# OpenCardiographySignalMeasuringDevice.net
KiCad netlist of a schematic drawn in EasyEDA Pro
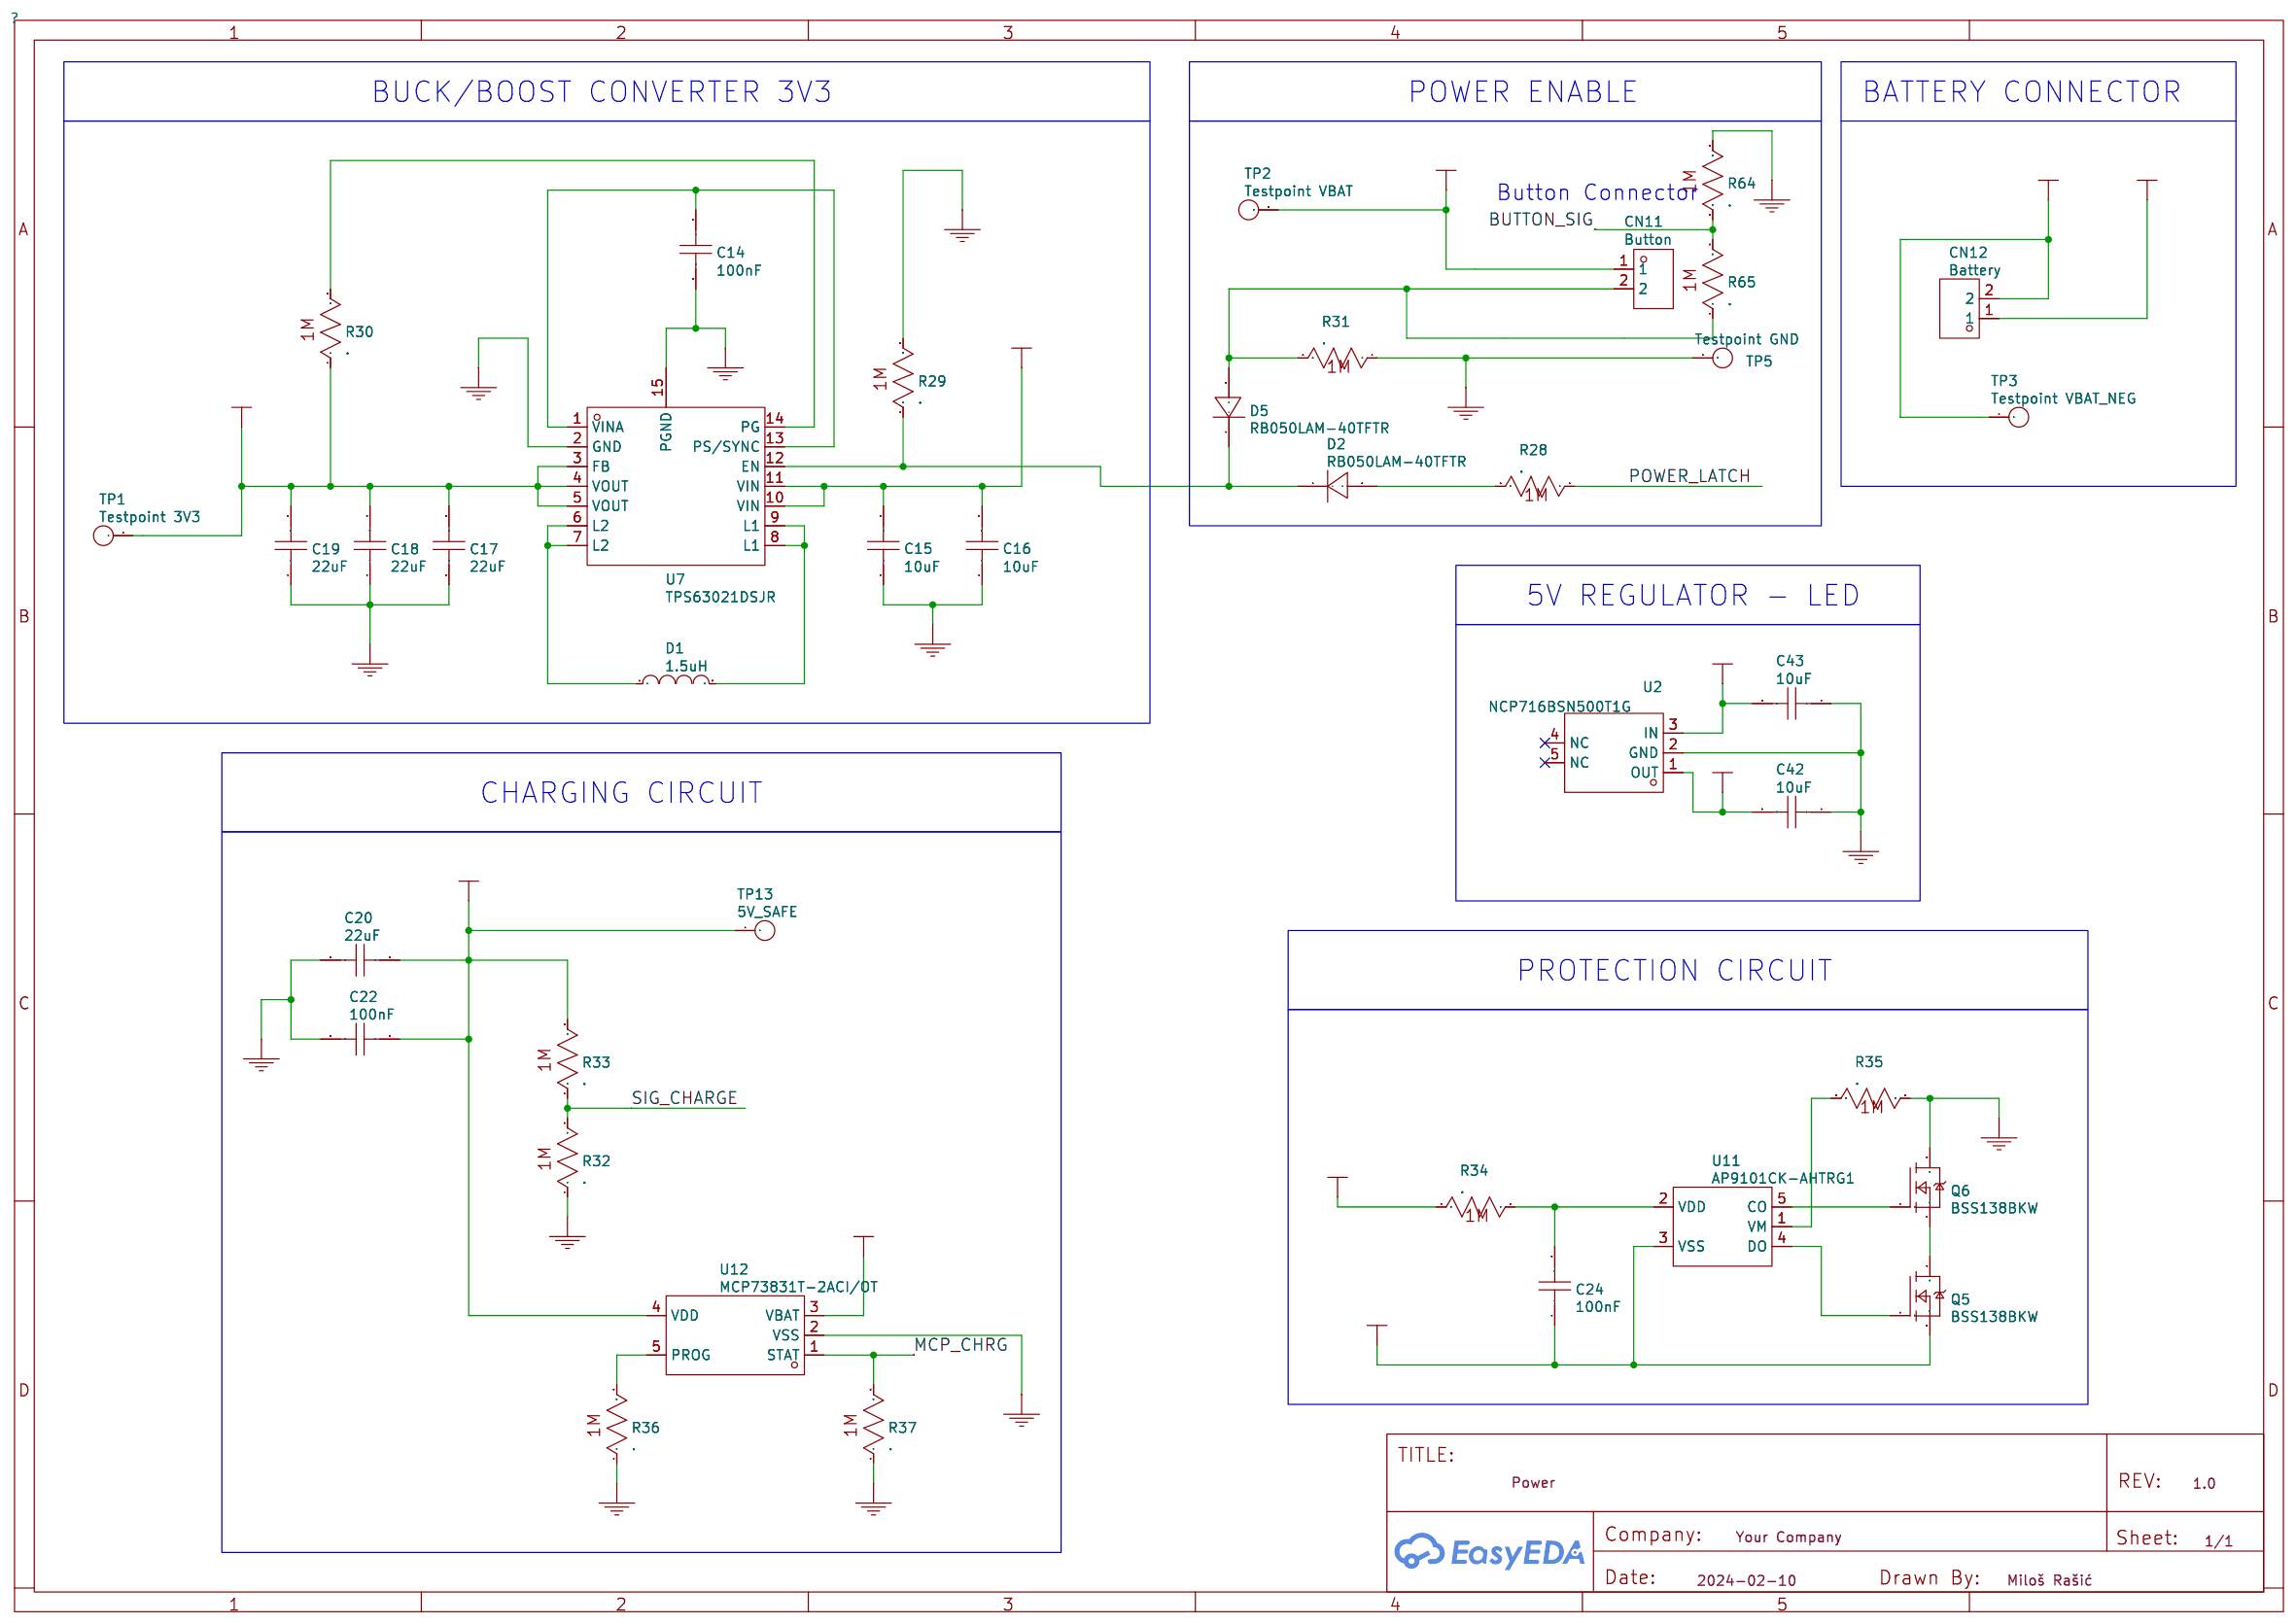
[diagram p0: Power]
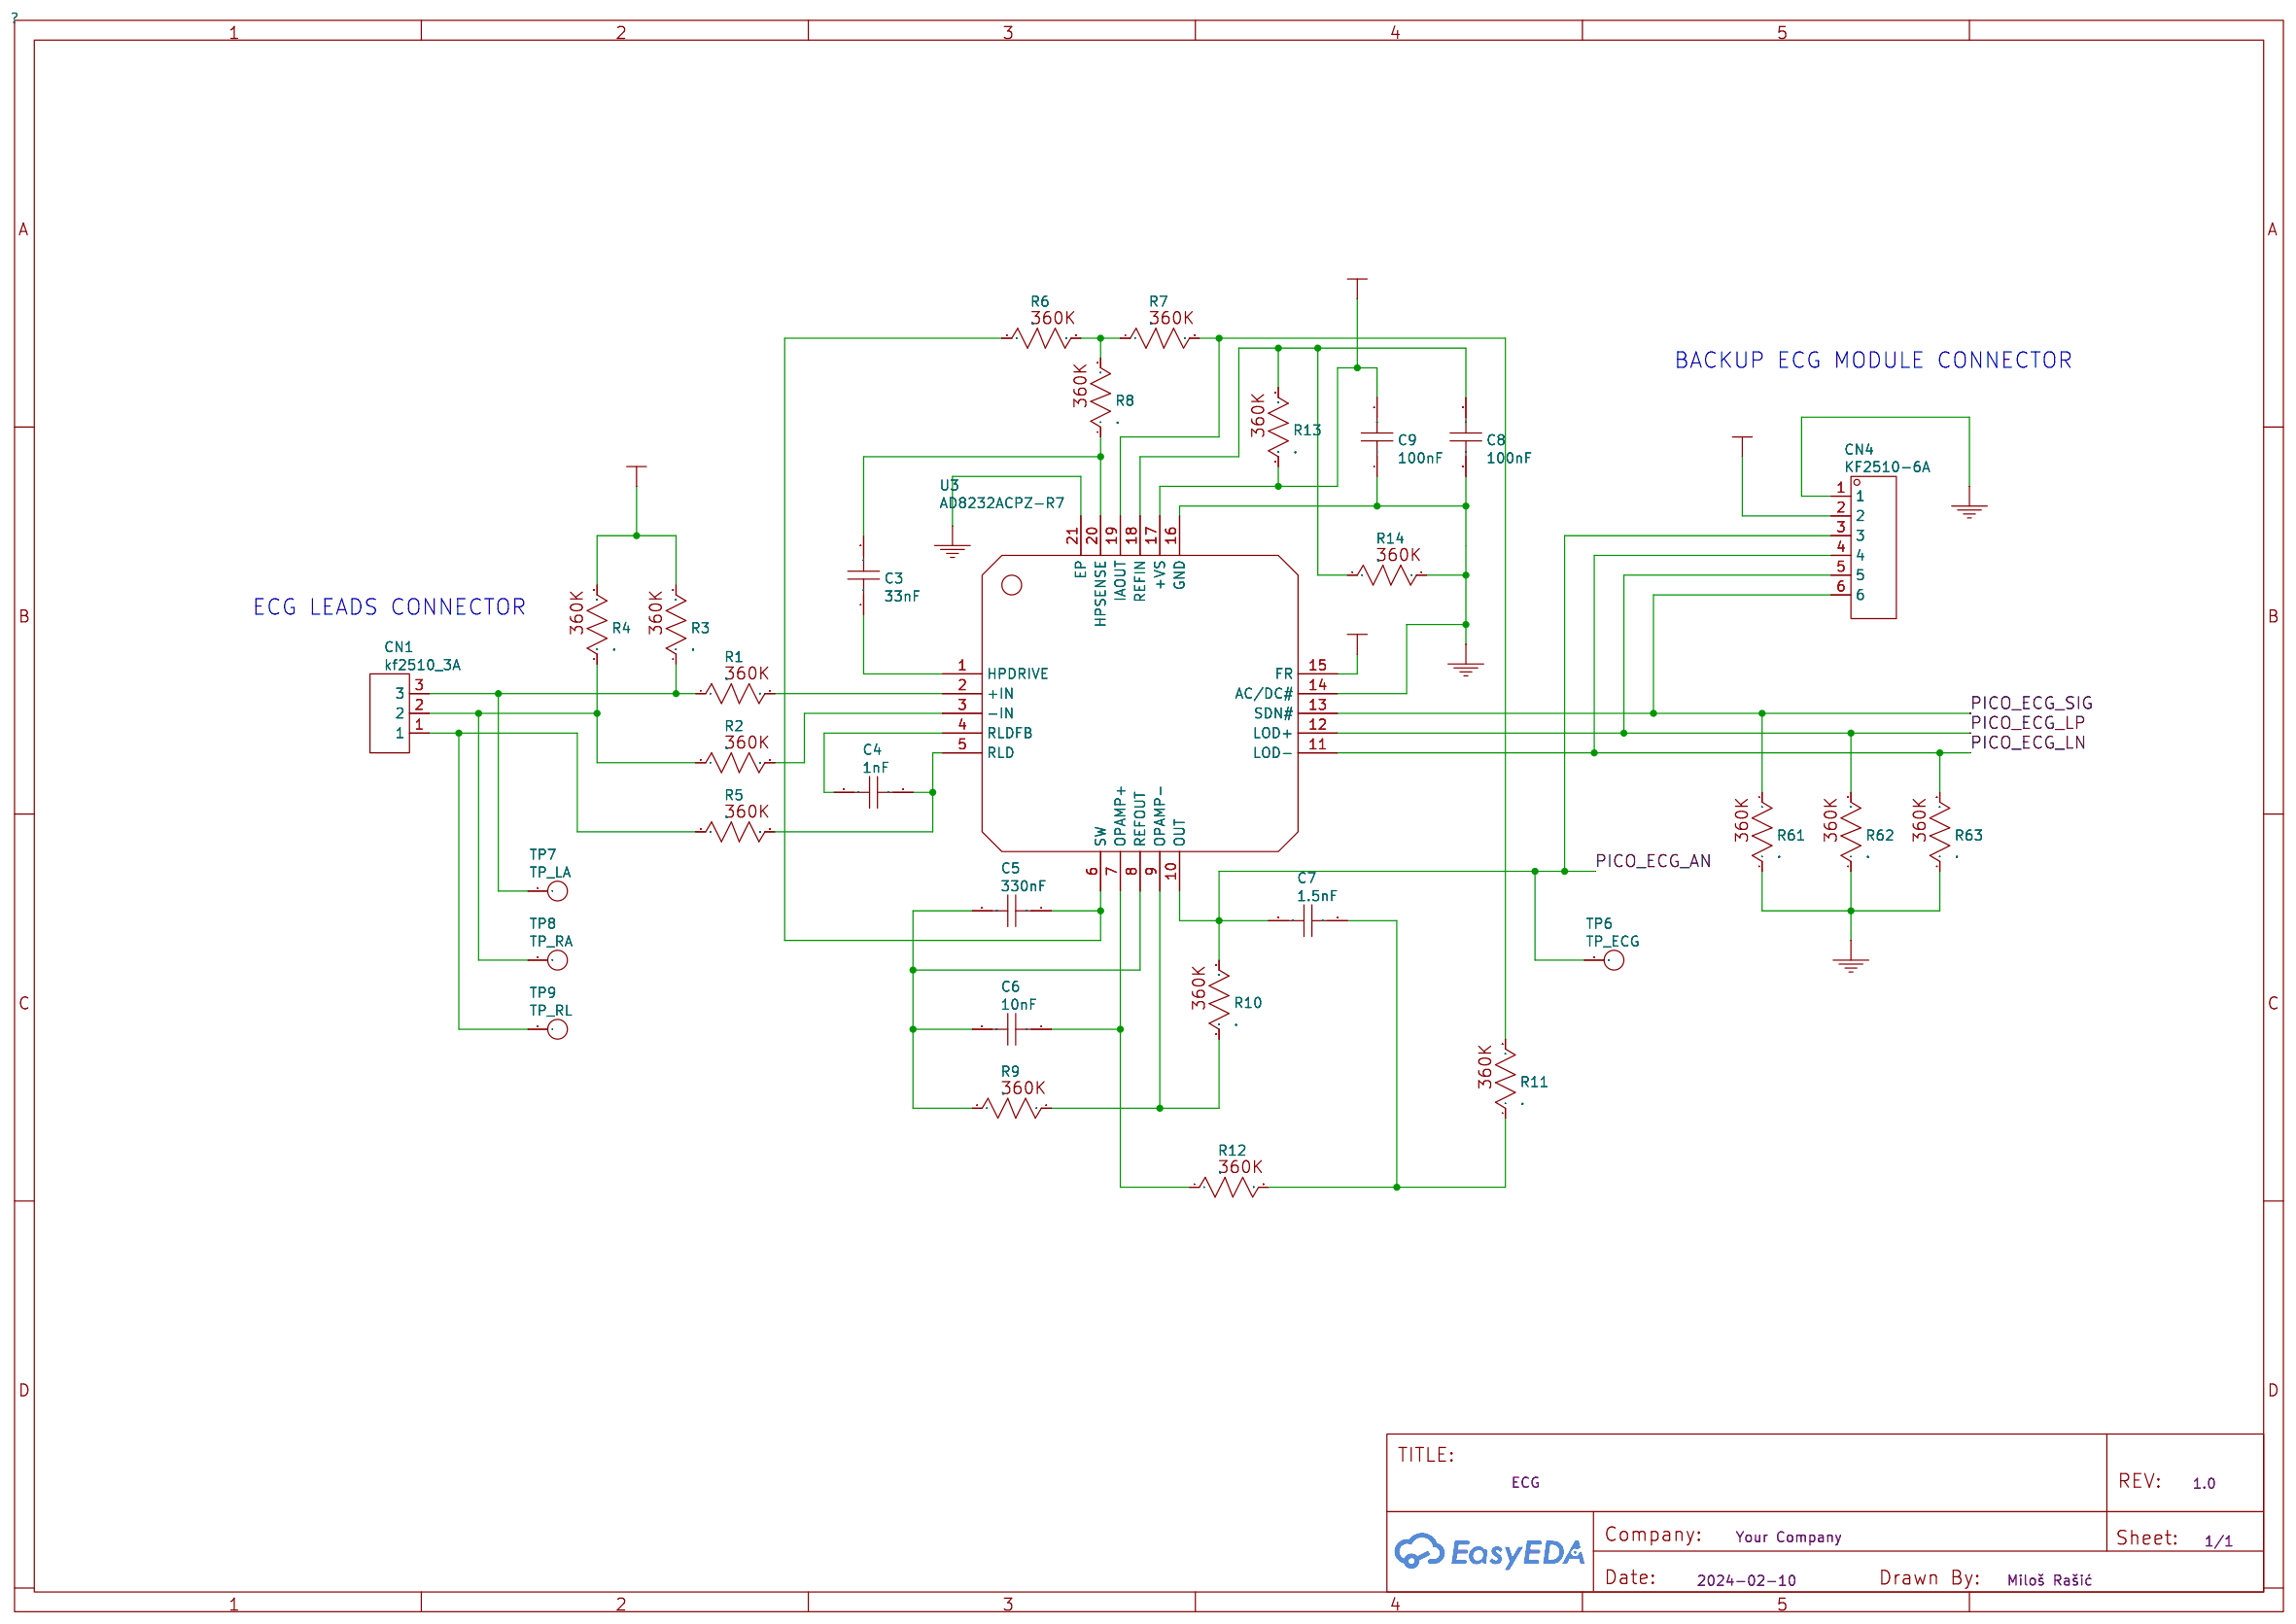
[diagram p1: ECG]
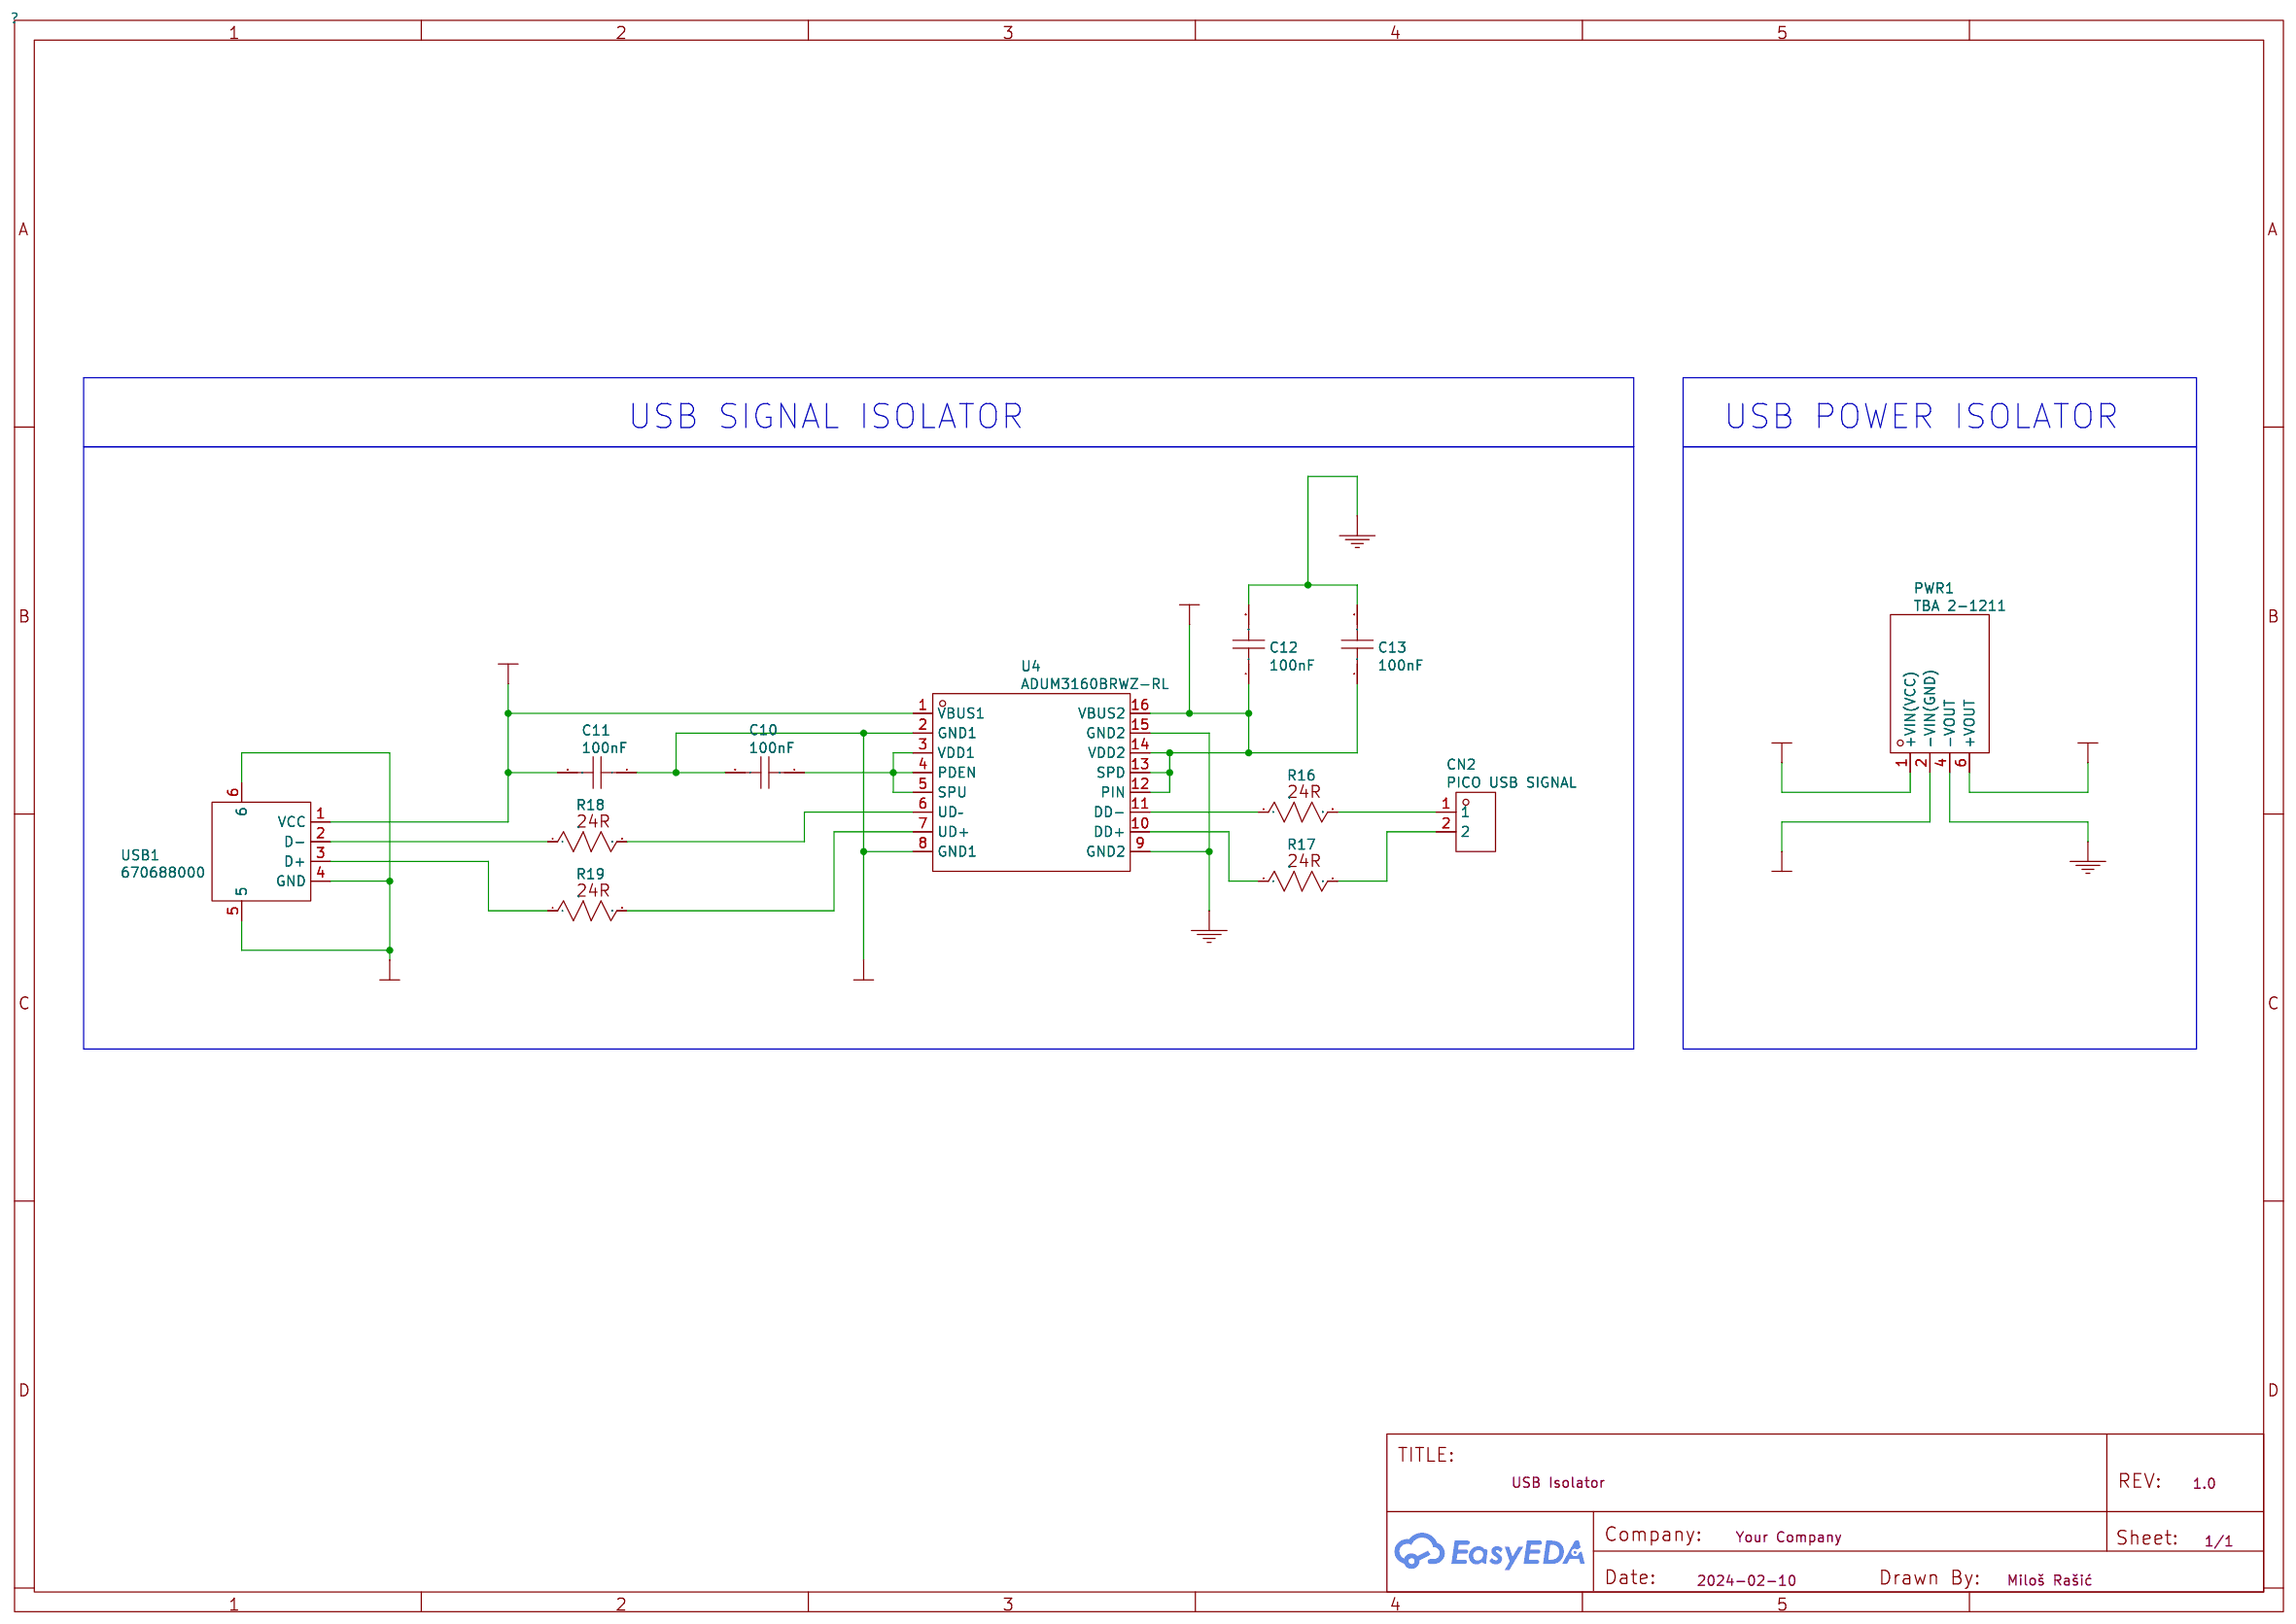
[diagram p2: USB Isolator]
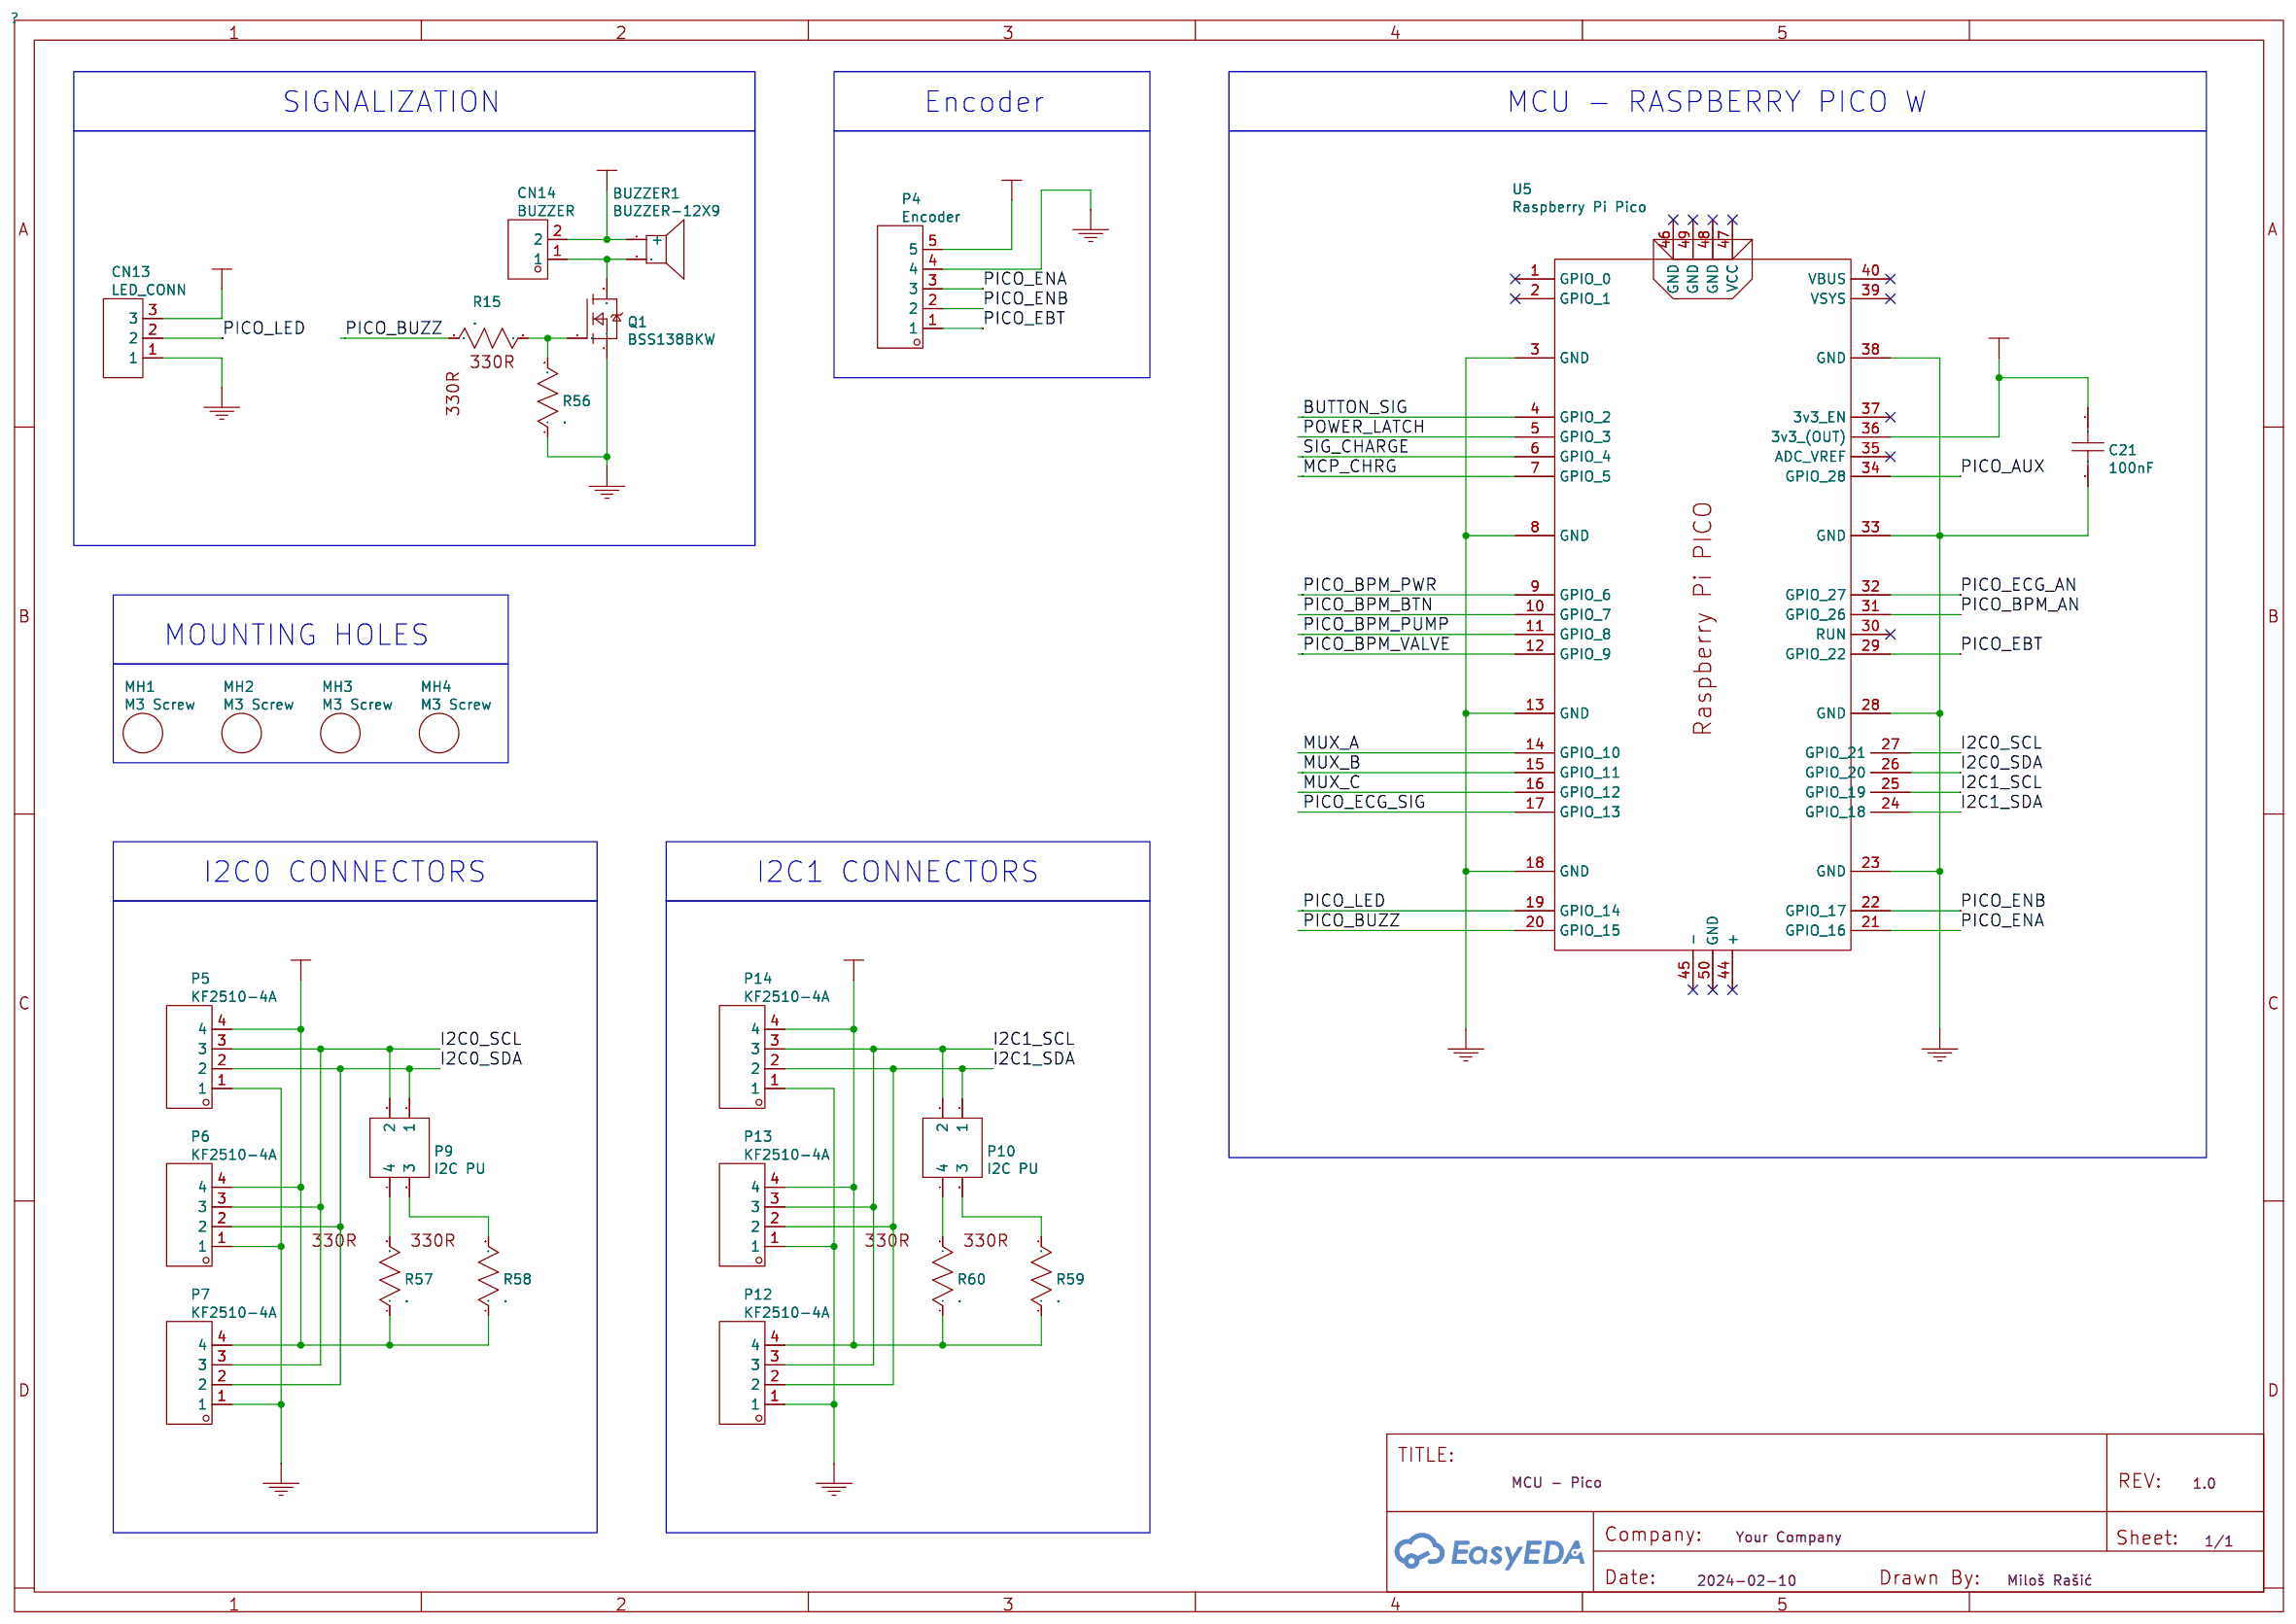
[diagram p3: MCU - Pico]
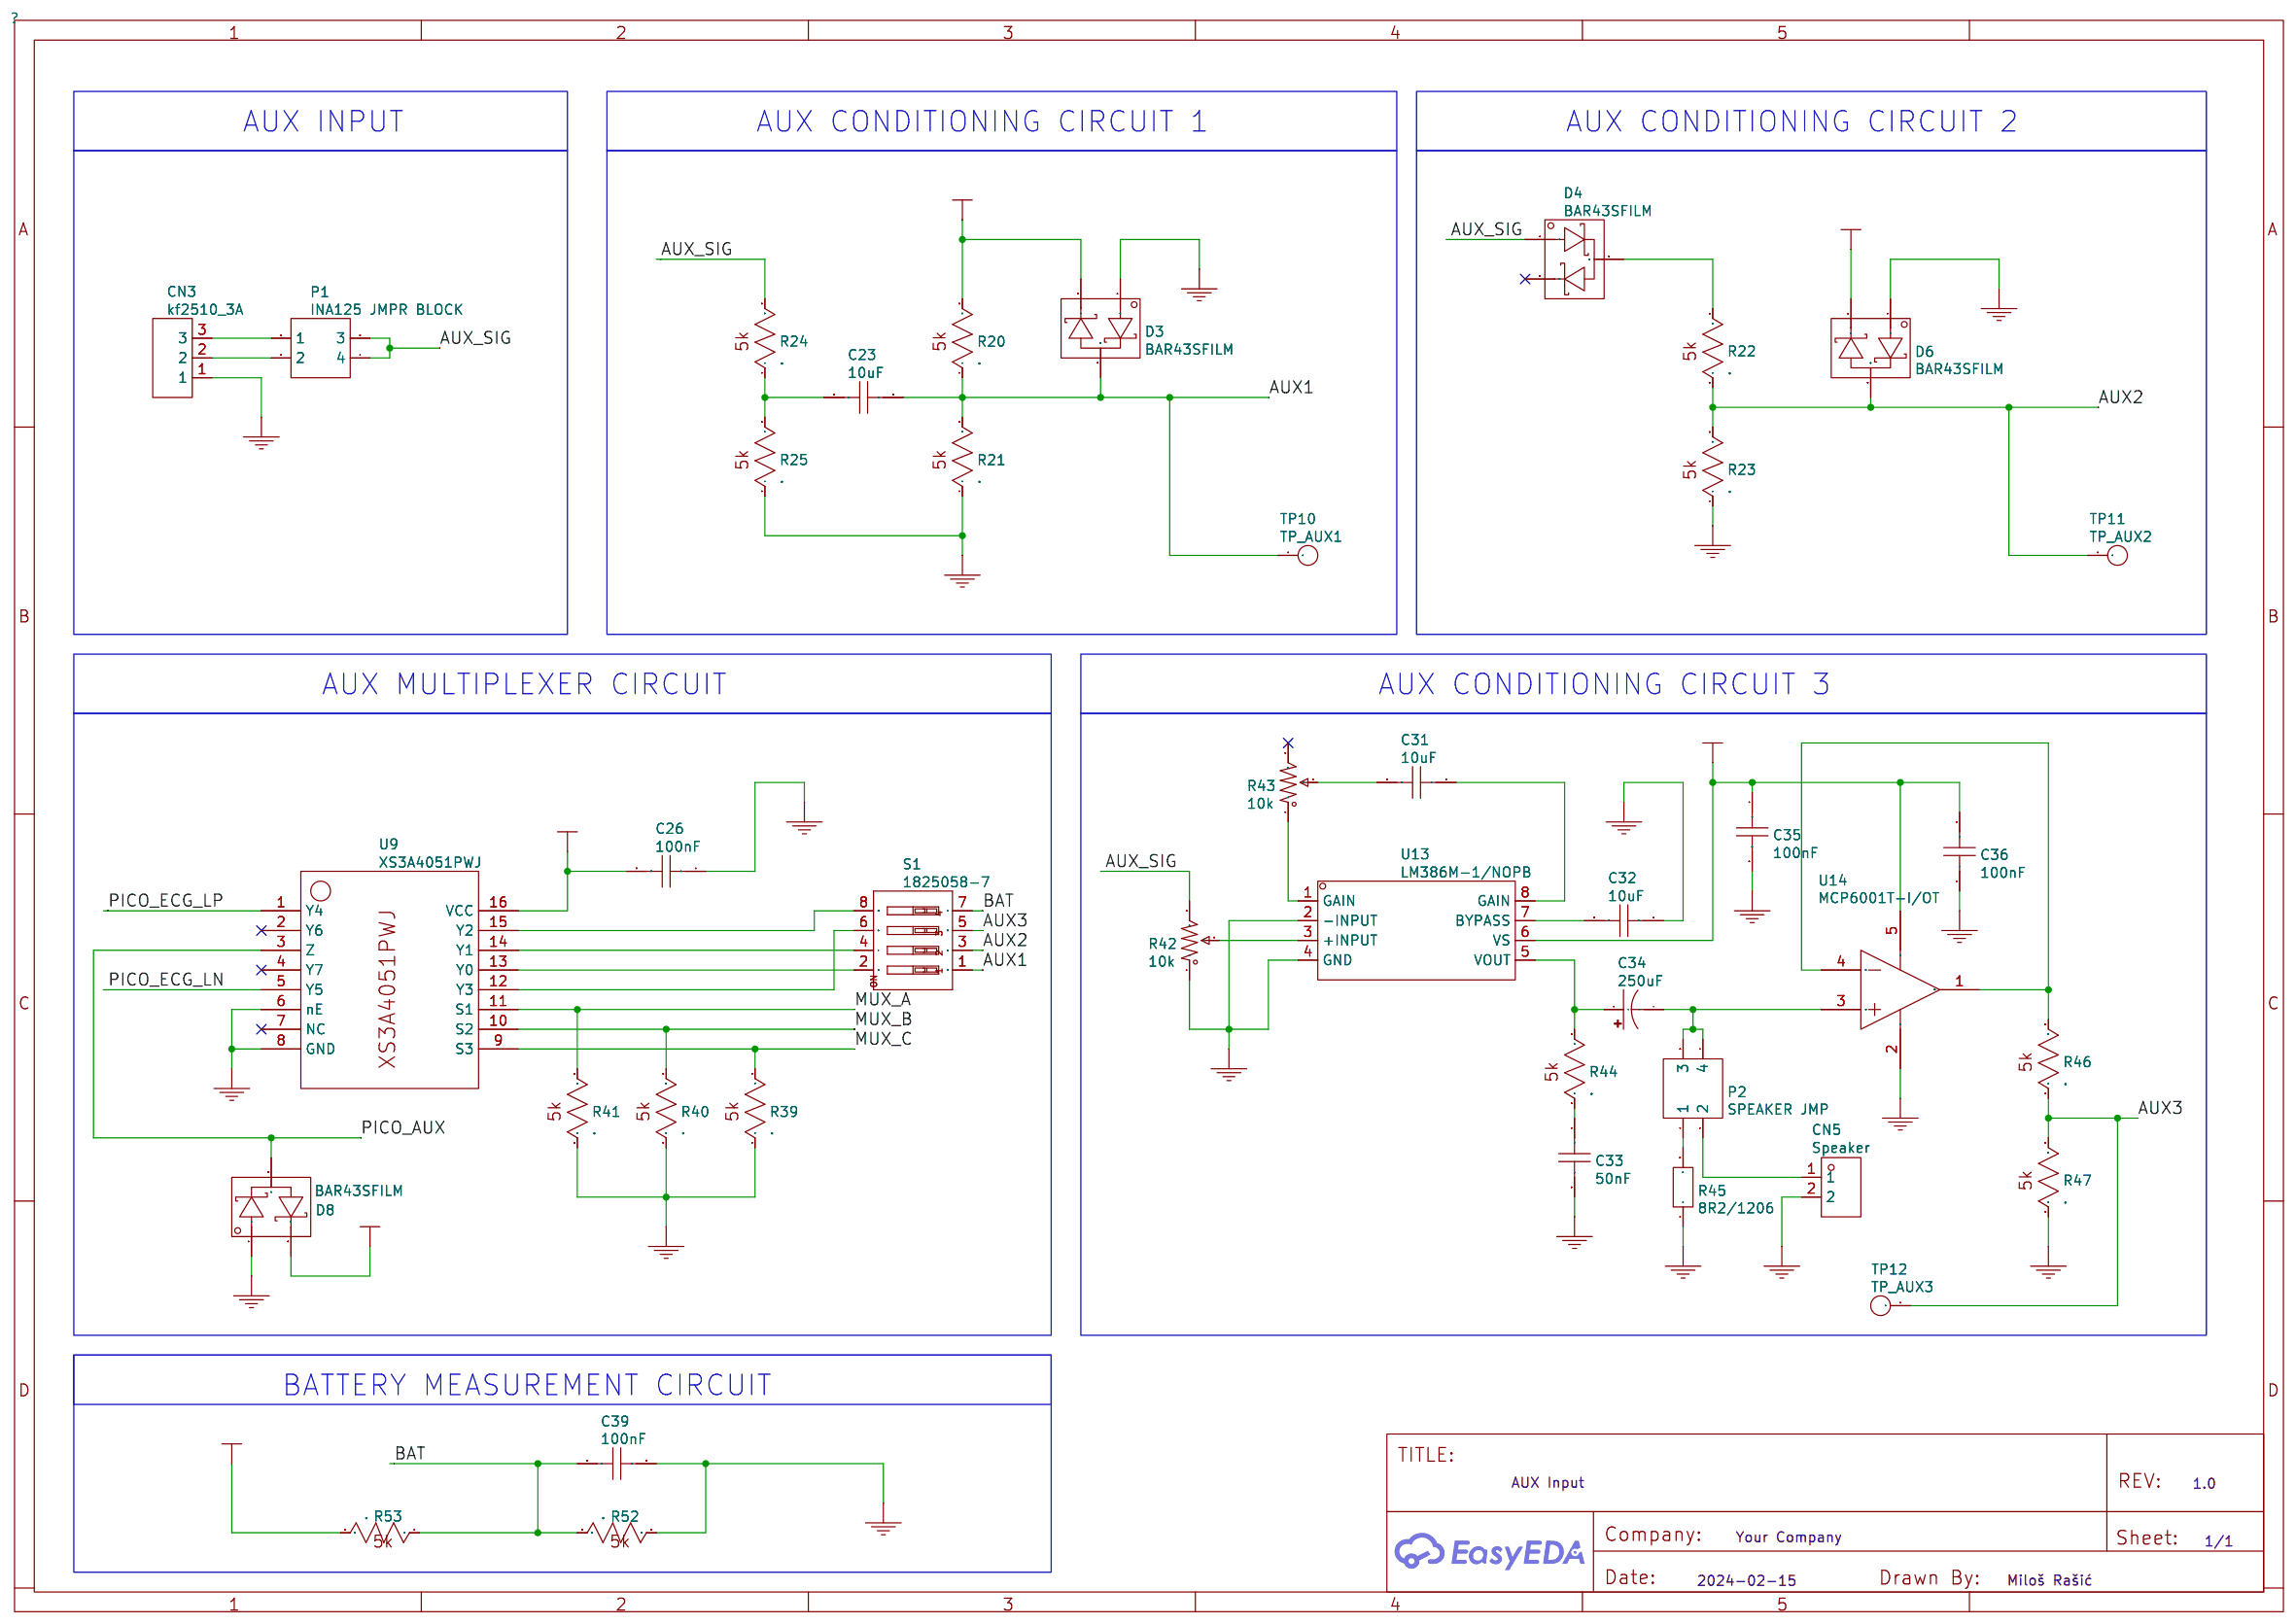
[diagram p4: AUX Input]
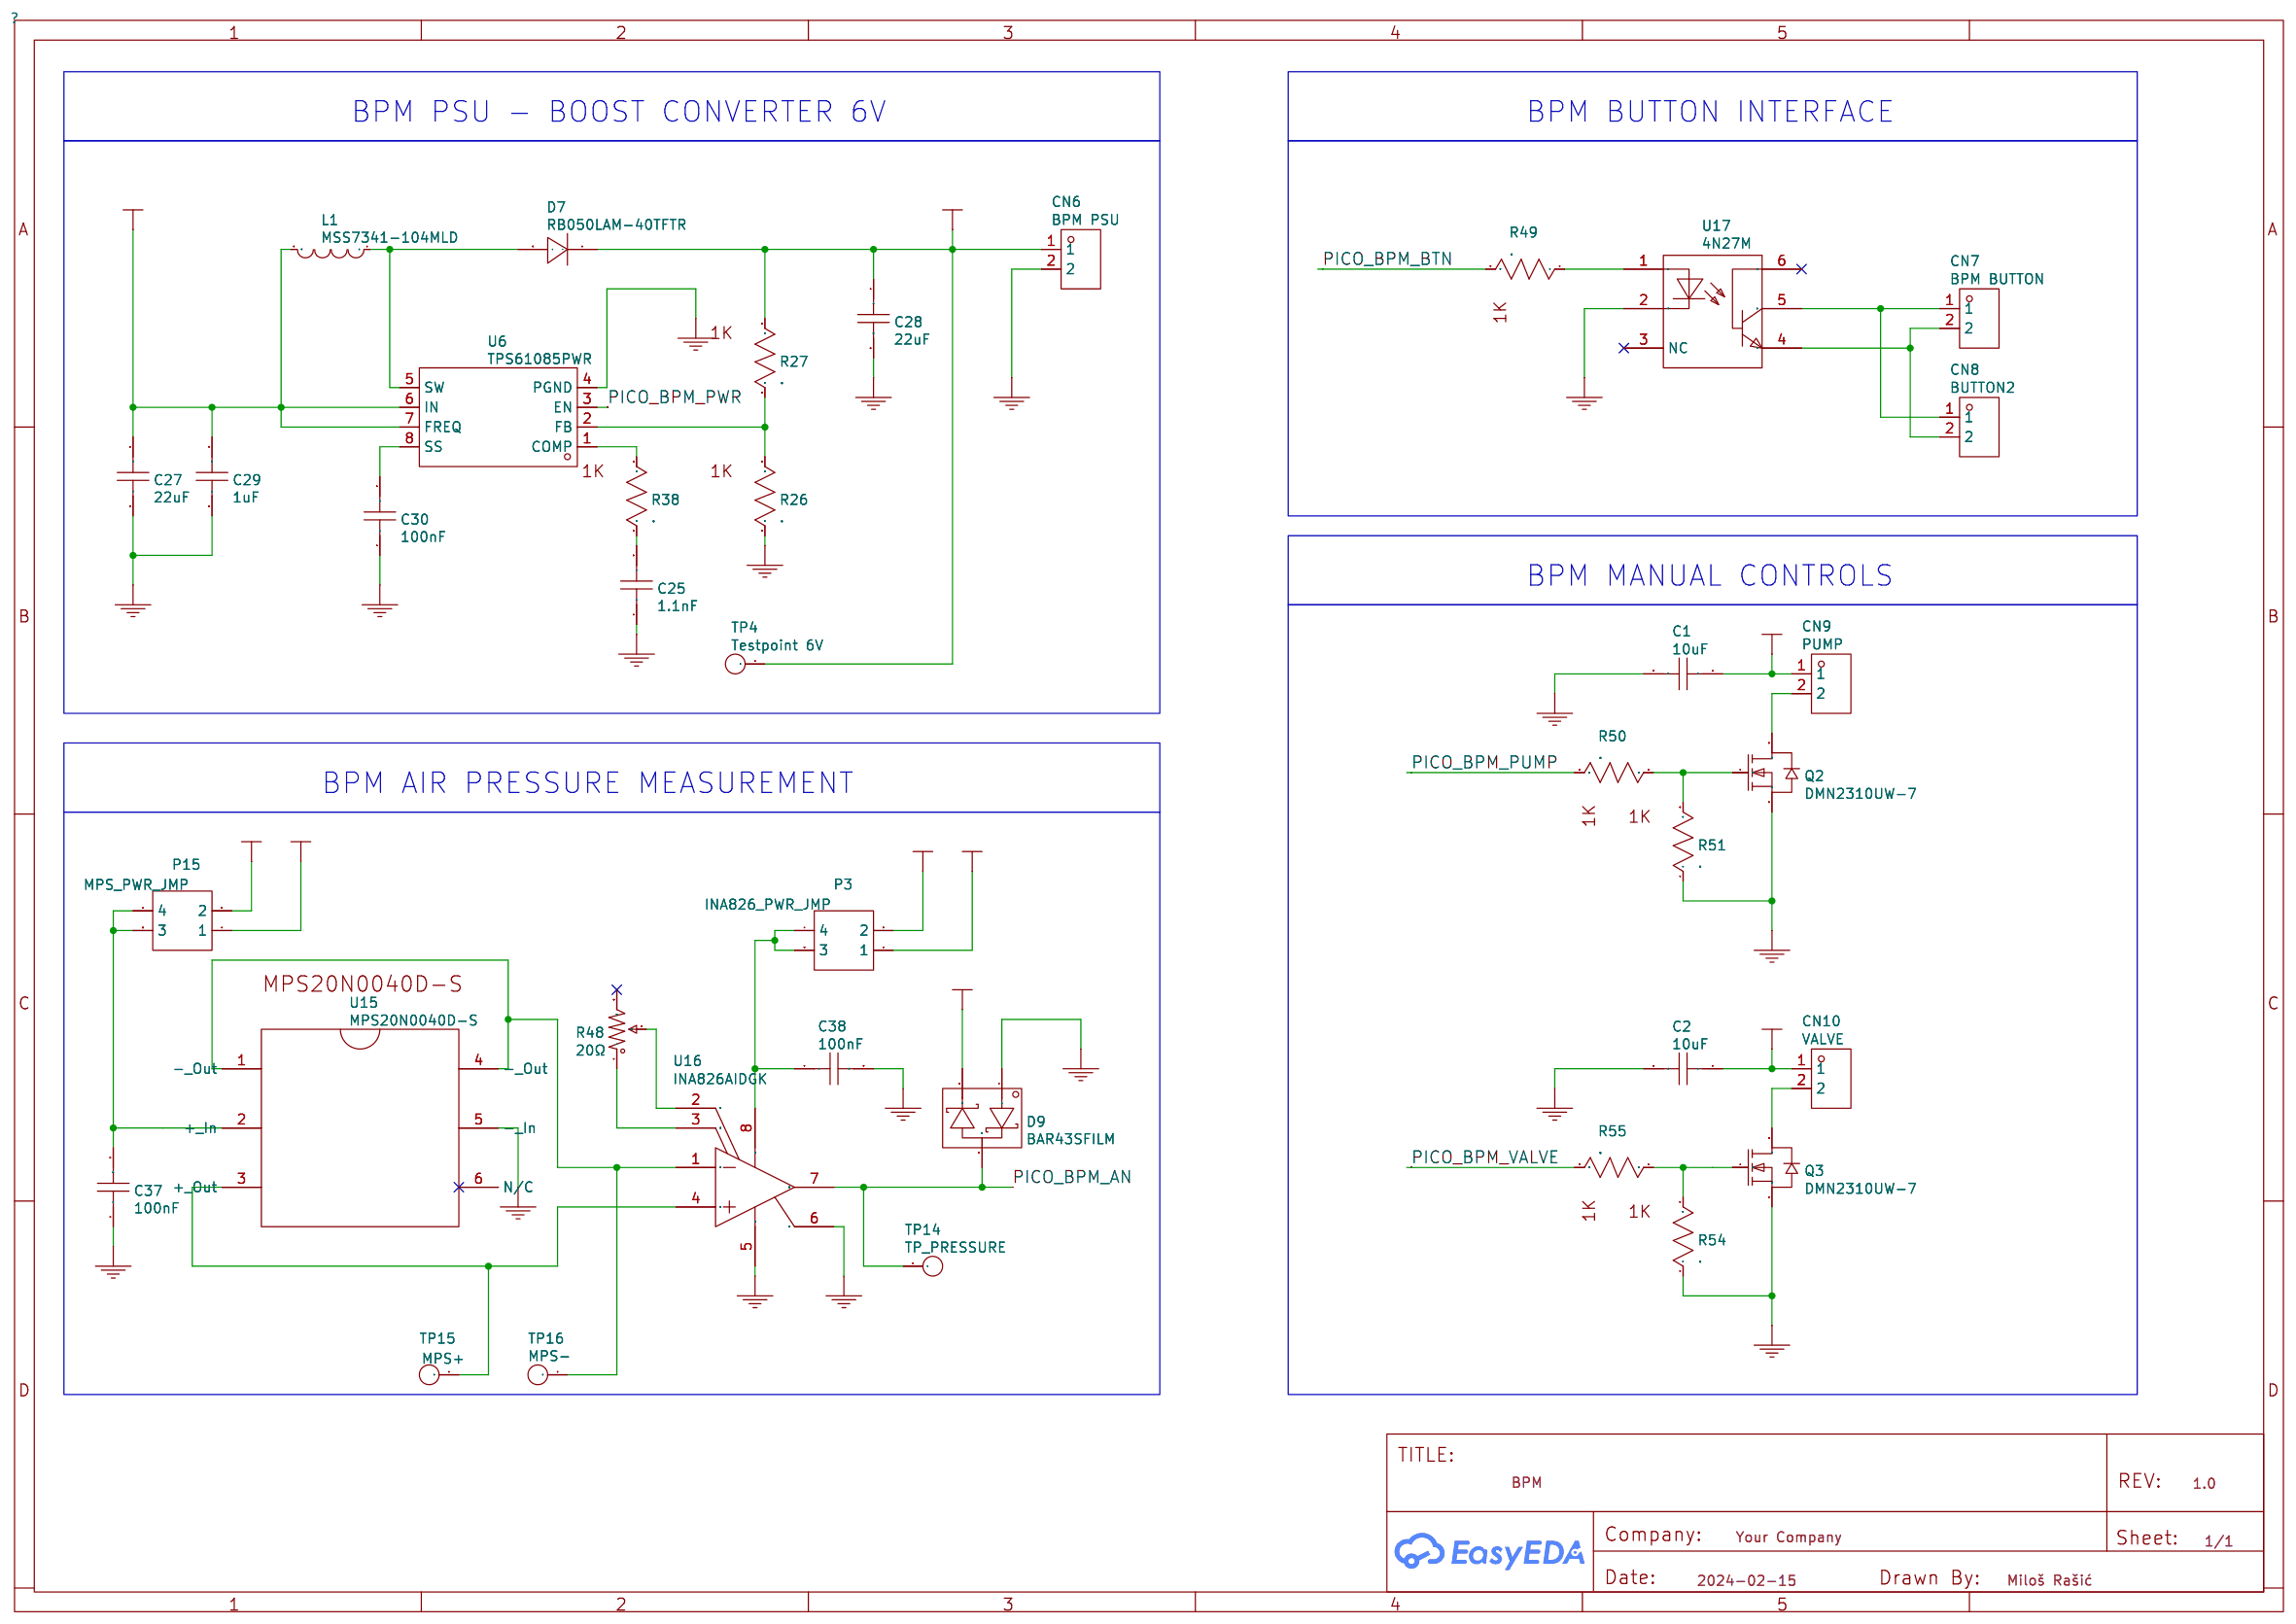
[diagram p5: BPM]

(export (version "E")
  (design (tool "Eeschema 10.0.6"))
  (components
    (comp (ref "C14")
      (value "100nF")
      (footprint "easyedapro:C0603")
      (fields (field (name "Manufacturer Part") "0603F104Z500CT") (field (name "Manufacturer") "Walsin(华新科)"))
      (libsource (lib "easyedapro") (part "100nF"))
    )
    (comp (ref "C15")
      (value "10uF")
      (footprint "easyedapro:C0805")
      (fields
        (field (name "Manufacturer Part") "C0805C106K4PAC7210")
        (field (name "Manufacturer") "KEMET(基美)")
      )
      (libsource (lib "easyedapro") (part "10uF"))
    )
    (comp (ref "C16")
      (value "10uF")
      (footprint "easyedapro:C0805")
      (fields
        (field (name "Manufacturer Part") "C0805C106K4PAC7210")
        (field (name "Manufacturer") "KEMET(基美)")
      )
      (libsource (lib "easyedapro") (part "10uF"))
    )
    (comp (ref "C17")
      (value "22uF")
      (footprint "easyedapro:C0805")
      (fields (field (name "Manufacturer Part") "C0805C226M9PACTU") (field (name "Manufacturer") "KEMET(基美)"))
      (libsource (lib "easyedapro") (part "22uF"))
    )
    (comp (ref "C18")
      (value "22uF")
      (footprint "easyedapro:C0805")
      (fields (field (name "Manufacturer Part") "C0805C226M9PACTU") (field (name "Manufacturer") "KEMET(基美)"))
      (libsource (lib "easyedapro") (part "22uF"))
    )
    (comp (ref "C19")
      (value "22uF")
      (footprint "easyedapro:C0805")
      (fields (field (name "Manufacturer Part") "C0805C226M9PACTU") (field (name "Manufacturer") "KEMET(基美)"))
      (libsource (lib "easyedapro") (part "22uF"))
    )
    (comp (ref "C20")
      (value "22uF")
      (footprint "easyedapro:C0805")
      (fields (field (name "Manufacturer Part") "C0805C226M9PACTU") (field (name "Manufacturer") "KEMET(基美)"))
      (libsource (lib "easyedapro") (part "22uF"))
    )
    (comp (ref "C22")
      (value "100nF")
      (footprint "easyedapro:C0603")
      (fields (field (name "Manufacturer Part") "0603F104Z500CT") (field (name "Manufacturer") "Walsin(华新科)"))
      (libsource (lib "easyedapro") (part "100nF"))
    )
    (comp (ref "C24")
      (value "100nF")
      (footprint "easyedapro:C0603")
      (fields (field (name "Manufacturer Part") "0603F104Z500CT") (field (name "Manufacturer") "Walsin(华新科)"))
      (libsource (lib "easyedapro") (part "100nF"))
    )
    (comp (ref "C42")
      (value "10uF")
      (footprint "easyedapro:C0805")
      (fields
        (field (name "Manufacturer Part") "C0805C106K4PAC7210")
        (field (name "Manufacturer") "KEMET(基美)")
      )
      (libsource (lib "easyedapro") (part "10uF"))
    )
    (comp (ref "C43")
      (value "10uF")
      (footprint "easyedapro:C0805")
      (fields
        (field (name "Manufacturer Part") "C0805C106K4PAC7210")
        (field (name "Manufacturer") "KEMET(基美)")
      )
      (libsource (lib "easyedapro") (part "10uF"))
    )
    (comp (ref "CN11")
      (value "Button")
      (footprint "easyedapro:CONN-TH_KF2510-2A")
      (fields (field (name "Manufacturer Part") "外接电机-KF2510直针 两个针间距2.54mm"))
      (libsource (lib "easyedapro") (part "Button"))
    )
    (comp (ref "CN12")
      (value "Battery")
      (footprint "easyedapro:CONN-TH_KF2510-2A")
      (fields (field (name "Manufacturer Part") "外接电机-KF2510直针 两个针间距2.54mm"))
      (libsource (lib "easyedapro") (part "Battery"))
    )
    (comp (ref "D1")
      (value "1.5uH")
      (footprint "easyedapro:IND-SMD_L3.0-W3.0-HPC3015TF-2R2M")
      (fields (field (name "Manufacturer Part") "SRN3015TA-1R5Y") (field (name "Manufacturer") "BOURNS"))
      (libsource (lib "easyedapro") (part "1.5uH"))
    )
    (comp (ref "D2")
      (value "RB050LAM-40TFTR")
      (footprint "easyedapro:SOD-128_L3.7-W2.5-LS4.7-RD")
      (fields (field (name "Manufacturer") "ROHM(罗姆)"))
      (libsource (lib "easyedapro") (part "RB050LAM-40TFTR"))
    )
    (comp (ref "D5")
      (value "RB050LAM-40TFTR")
      (footprint "easyedapro:SOD-128_L3.7-W2.5-LS4.7-RD")
      (fields (field (name "Manufacturer") "ROHM(罗姆)"))
      (libsource (lib "easyedapro") (part "RB050LAM-40TFTR"))
    )
    (comp (ref "Q5")
      (value "BSS138BKW")
      (footprint "easyedapro:SOT323")
      (libsource (lib "easyedapro") (part "BSS138BKW"))
    )
    (comp (ref "Q6")
      (value "BSS138BKW")
      (footprint "easyedapro:SOT323")
      (libsource (lib "easyedapro") (part "BSS138BKW"))
    )
    (comp (ref "R28")
      (value ".")
      (footprint "easyedapro:20K OHM RESISTOR (0603) SMD - CRCW060320K0FKEAC")
      (fields
        (field (name "Manufacturer Part") "71-CRCW060320K0FKEAC")
        (field (name "Manufacturer") "Vishay/Dale")
      )
      (libsource (lib "easyedapro") (part "."))
    )
    (comp (ref "R29")
      (value ".")
      (footprint "easyedapro:20K OHM RESISTOR (0603) SMD - CRCW060320K0FKEAC")
      (fields
        (field (name "Manufacturer Part") "71-CRCW060320K0FKEAC")
        (field (name "Manufacturer") "Vishay/Dale")
      )
      (libsource (lib "easyedapro") (part "."))
    )
    (comp (ref "R30")
      (value ".")
      (footprint "easyedapro:20K OHM RESISTOR (0603) SMD - CRCW060320K0FKEAC")
      (fields
        (field (name "Manufacturer Part") "71-CRCW060320K0FKEAC")
        (field (name "Manufacturer") "Vishay/Dale")
      )
      (libsource (lib "easyedapro") (part "."))
    )
    (comp (ref "R31")
      (value ".")
      (footprint "easyedapro:20K OHM RESISTOR (0603) SMD - CRCW060320K0FKEAC")
      (fields
        (field (name "Manufacturer Part") "71-CRCW060320K0FKEAC")
        (field (name "Manufacturer") "Vishay/Dale")
      )
      (libsource (lib "easyedapro") (part "."))
    )
    (comp (ref "R32")
      (value ".")
      (footprint "easyedapro:20K OHM RESISTOR (0603) SMD - CRCW060320K0FKEAC")
      (fields
        (field (name "Manufacturer Part") "71-CRCW060320K0FKEAC")
        (field (name "Manufacturer") "Vishay/Dale")
      )
      (libsource (lib "easyedapro") (part "."))
    )
    (comp (ref "R33")
      (value ".")
      (footprint "easyedapro:20K OHM RESISTOR (0603) SMD - CRCW060320K0FKEAC")
      (fields
        (field (name "Manufacturer Part") "71-CRCW060320K0FKEAC")
        (field (name "Manufacturer") "Vishay/Dale")
      )
      (libsource (lib "easyedapro") (part "."))
    )
    (comp (ref "R34")
      (value ".")
      (footprint "easyedapro:20K OHM RESISTOR (0603) SMD - CRCW060320K0FKEAC")
      (fields
        (field (name "Manufacturer Part") "71-CRCW060320K0FKEAC")
        (field (name "Manufacturer") "Vishay/Dale")
      )
      (libsource (lib "easyedapro") (part "."))
    )
    (comp (ref "R35")
      (value ".")
      (footprint "easyedapro:20K OHM RESISTOR (0603) SMD - CRCW060320K0FKEAC")
      (fields
        (field (name "Manufacturer Part") "71-CRCW060320K0FKEAC")
        (field (name "Manufacturer") "Vishay/Dale")
      )
      (libsource (lib "easyedapro") (part "."))
    )
    (comp (ref "R36")
      (value ".")
      (footprint "easyedapro:20K OHM RESISTOR (0603) SMD - CRCW060320K0FKEAC")
      (fields
        (field (name "Manufacturer Part") "71-CRCW060320K0FKEAC")
        (field (name "Manufacturer") "Vishay/Dale")
      )
      (libsource (lib "easyedapro") (part "."))
    )
    (comp (ref "R37")
      (value ".")
      (footprint "easyedapro:20K OHM RESISTOR (0603) SMD - CRCW060320K0FKEAC")
      (fields
        (field (name "Manufacturer Part") "71-CRCW060320K0FKEAC")
        (field (name "Manufacturer") "Vishay/Dale")
      )
      (libsource (lib "easyedapro") (part "."))
    )
    (comp (ref "R64")
      (value ".")
      (footprint "easyedapro:20K OHM RESISTOR (0603) SMD - CRCW060320K0FKEAC")
      (fields
        (field (name "Manufacturer Part") "71-CRCW060320K0FKEAC")
        (field (name "Manufacturer") "Vishay/Dale")
      )
      (libsource (lib "easyedapro") (part "."))
    )
    (comp (ref "R65")
      (value ".")
      (footprint "easyedapro:20K OHM RESISTOR (0603) SMD - CRCW060320K0FKEAC")
      (fields
        (field (name "Manufacturer Part") "71-CRCW060320K0FKEAC")
        (field (name "Manufacturer") "Vishay/Dale")
      )
      (libsource (lib "easyedapro") (part "."))
    )
    (comp (ref "TP1")
      (value "Testpoint 3V3")
      (footprint "easyedapro:TESTPOINT")
      (libsource (lib "easyedapro") (part "Testpoint 3V3"))
    )
    (comp (ref "TP2")
      (value "Testpoint VBAT")
      (footprint "easyedapro:TESTPOINT")
      (libsource (lib "easyedapro") (part "Testpoint VBAT"))
    )
    (comp (ref "TP3")
      (value "Testpoint VBAT_NEG")
      (footprint "easyedapro:TESTPOINT")
      (libsource (lib "easyedapro") (part "Testpoint VBAT_NEG"))
    )
    (comp (ref "TP5")
      (value "Testpoint GND")
      (footprint "easyedapro:TESTPOINT")
      (libsource (lib "easyedapro") (part "Testpoint GND"))
    )
    (comp (ref "TP13")
      (value "5V_SAFE")
      (footprint "easyedapro:TESTPOINT")
      (libsource (lib "easyedapro") (part "5V_SAFE"))
    )
    (comp (ref "U2")
      (value "NCP716BSN500T1G")
      (footprint "easyedapro:TSOP-5_L3.0-W1.5-P0.95-LS2.8-BL")
      (fields (field (name "Manufacturer") "onsemi(安森美)"))
      (libsource (lib "easyedapro") (part "NCP716BSN500T1G"))
    )
    (comp (ref "U7")
      (value "TPS63021DSJR")
      (footprint "easyedapro:VSON-14_L4.0-W3.0-P0.50-BL-EP_TI_DSJ")
      (fields (field (name "Manufacturer") "TI(德州仪器)"))
      (libsource (lib "easyedapro") (part "TPS63021DSJR"))
    )
    (comp (ref "U11")
      (value "AP9101CK-AHTRG1")
      (footprint "easyedapro:SOT-23-5_L3.0-W1.7-P0.95-LS2.8-BL")
      (fields (field (name "Manufacturer") "DIODES(美台)"))
      (libsource (lib "easyedapro") (part "AP9101CK-AHTRG1"))
    )
    (comp (ref "U12")
      (value "MCP73831T-2ACI/OT")
      (footprint "easyedapro:SOT-23-5_L3.0-W1.7-P0.95-LS2.8-BL")
      (fields (field (name "Manufacturer") "MICROCHIP(美国微芯)"))
      (libsource (lib "easyedapro") (part "MCP73831T-2ACI/OT"))
    )
    (comp (ref "C3")
      (value "33nF")
      (footprint "easyedapro:C0603")
      (fields (field (name "Manufacturer Part") "0603F104Z500CT") (field (name "Manufacturer") "Walsin(华新科)"))
      (libsource (lib "easyedapro") (part "33nF"))
    )
    (comp (ref "C4")
      (value "1nF")
      (footprint "easyedapro:C0603")
      (fields (field (name "Manufacturer Part") "0603F104Z500CT") (field (name "Manufacturer") "Walsin(华新科)"))
      (libsource (lib "easyedapro") (part "1nF"))
    )
    (comp (ref "C5")
      (value "330nF")
      (footprint "easyedapro:C0603")
      (fields (field (name "Manufacturer Part") "0603F104Z500CT") (field (name "Manufacturer") "Walsin(华新科)"))
      (libsource (lib "easyedapro") (part "330nF"))
    )
    (comp (ref "C6")
      (value "10nF")
      (footprint "easyedapro:C0603")
      (fields (field (name "Manufacturer Part") "0603F104Z500CT") (field (name "Manufacturer") "Walsin(华新科)"))
      (libsource (lib "easyedapro") (part "10nF"))
    )
    (comp (ref "C7")
      (value "1.5nF")
      (footprint "easyedapro:C0603")
      (fields (field (name "Manufacturer Part") "0603F104Z500CT") (field (name "Manufacturer") "Walsin(华新科)"))
      (libsource (lib "easyedapro") (part "1.5nF"))
    )
    (comp (ref "C8")
      (value "100nF")
      (footprint "easyedapro:C0603")
      (fields (field (name "Manufacturer Part") "0603F104Z500CT") (field (name "Manufacturer") "Walsin(华新科)"))
      (libsource (lib "easyedapro") (part "100nF"))
    )
    (comp (ref "C9")
      (value "100nF")
      (footprint "easyedapro:C0603")
      (fields (field (name "Manufacturer Part") "0603F104Z500CT") (field (name "Manufacturer") "Walsin(华新科)"))
      (libsource (lib "easyedapro") (part "100nF"))
    )
    (comp (ref "CN1")
      (value "kf2510_3A")
      (footprint "easyedapro:CONN-TH_3P-P2.00_KF2510_3A")
      (fields (field (name "Manufacturer Part") "2510-3A") (field (name "Manufacturer") "BOOMELE(博穆精密)"))
      (libsource (lib "easyedapro") (part "kf2510_3A"))
    )
    (comp (ref "CN4")
      (value "KF2510-6A")
      (footprint "easyedapro:CONN-TH_KF2510-6A")
      (fields (field (name "Manufacturer") "ReliaPro"))
      (libsource (lib "easyedapro") (part "KF2510-6A"))
    )
    (comp (ref "R1")
      (value ".")
      (footprint "easyedapro:20K OHM RESISTOR (0603) SMD - CRCW060320K0FKEAC")
      (fields
        (field (name "Manufacturer Part") "71-CRCW060320K0FKEAC")
        (field (name "Manufacturer") "Vishay/Dale")
      )
      (libsource (lib "easyedapro") (part "."))
    )
    (comp (ref "R2")
      (value ".")
      (footprint "easyedapro:20K OHM RESISTOR (0603) SMD - CRCW060320K0FKEAC")
      (fields
        (field (name "Manufacturer Part") "71-CRCW060320K0FKEAC")
        (field (name "Manufacturer") "Vishay/Dale")
      )
      (libsource (lib "easyedapro") (part "."))
    )
    (comp (ref "R3")
      (value ".")
      (footprint "easyedapro:20K OHM RESISTOR (0603) SMD - CRCW060320K0FKEAC")
      (fields
        (field (name "Manufacturer Part") "71-CRCW060320K0FKEAC")
        (field (name "Manufacturer") "Vishay/Dale")
      )
      (libsource (lib "easyedapro") (part "."))
    )
    (comp (ref "R4")
      (value ".")
      (footprint "easyedapro:20K OHM RESISTOR (0603) SMD - CRCW060320K0FKEAC")
      (fields
        (field (name "Manufacturer Part") "71-CRCW060320K0FKEAC")
        (field (name "Manufacturer") "Vishay/Dale")
      )
      (libsource (lib "easyedapro") (part "."))
    )
    (comp (ref "R5")
      (value ".")
      (footprint "easyedapro:20K OHM RESISTOR (0603) SMD - CRCW060320K0FKEAC")
      (fields
        (field (name "Manufacturer Part") "71-CRCW060320K0FKEAC")
        (field (name "Manufacturer") "Vishay/Dale")
      )
      (libsource (lib "easyedapro") (part "."))
    )
    (comp (ref "R6")
      (value ".")
      (footprint "easyedapro:20K OHM RESISTOR (0603) SMD - CRCW060320K0FKEAC")
      (fields
        (field (name "Manufacturer Part") "71-CRCW060320K0FKEAC")
        (field (name "Manufacturer") "Vishay/Dale")
      )
      (libsource (lib "easyedapro") (part "."))
    )
    (comp (ref "R7")
      (value ".")
      (footprint "easyedapro:20K OHM RESISTOR (0603) SMD - CRCW060320K0FKEAC")
      (fields
        (field (name "Manufacturer Part") "71-CRCW060320K0FKEAC")
        (field (name "Manufacturer") "Vishay/Dale")
      )
      (libsource (lib "easyedapro") (part "."))
    )
    (comp (ref "R8")
      (value ".")
      (footprint "easyedapro:20K OHM RESISTOR (0603) SMD - CRCW060320K0FKEAC")
      (fields
        (field (name "Manufacturer Part") "71-CRCW060320K0FKEAC")
        (field (name "Manufacturer") "Vishay/Dale")
      )
      (libsource (lib "easyedapro") (part "."))
    )
    (comp (ref "R9")
      (value ".")
      (footprint "easyedapro:20K OHM RESISTOR (0603) SMD - CRCW060320K0FKEAC")
      (fields
        (field (name "Manufacturer Part") "71-CRCW060320K0FKEAC")
        (field (name "Manufacturer") "Vishay/Dale")
      )
      (libsource (lib "easyedapro") (part "."))
    )
    (comp (ref "R10")
      (value ".")
      (footprint "easyedapro:20K OHM RESISTOR (0603) SMD - CRCW060320K0FKEAC")
      (fields
        (field (name "Manufacturer Part") "71-CRCW060320K0FKEAC")
        (field (name "Manufacturer") "Vishay/Dale")
      )
      (libsource (lib "easyedapro") (part "."))
    )
    (comp (ref "R11")
      (value ".")
      (footprint "easyedapro:20K OHM RESISTOR (0603) SMD - CRCW060320K0FKEAC")
      (fields
        (field (name "Manufacturer Part") "71-CRCW060320K0FKEAC")
        (field (name "Manufacturer") "Vishay/Dale")
      )
      (libsource (lib "easyedapro") (part "."))
    )
    (comp (ref "R12")
      (value ".")
      (footprint "easyedapro:20K OHM RESISTOR (0603) SMD - CRCW060320K0FKEAC")
      (fields
        (field (name "Manufacturer Part") "71-CRCW060320K0FKEAC")
        (field (name "Manufacturer") "Vishay/Dale")
      )
      (libsource (lib "easyedapro") (part "."))
    )
    (comp (ref "R13")
      (value ".")
      (footprint "easyedapro:20K OHM RESISTOR (0603) SMD - CRCW060320K0FKEAC")
      (fields
        (field (name "Manufacturer Part") "71-CRCW060320K0FKEAC")
        (field (name "Manufacturer") "Vishay/Dale")
      )
      (libsource (lib "easyedapro") (part "."))
    )
    (comp (ref "R14")
      (value ".")
      (footprint "easyedapro:20K OHM RESISTOR (0603) SMD - CRCW060320K0FKEAC")
      (fields
        (field (name "Manufacturer Part") "71-CRCW060320K0FKEAC")
        (field (name "Manufacturer") "Vishay/Dale")
      )
      (libsource (lib "easyedapro") (part "."))
    )
    (comp (ref "R61")
      (value ".")
      (footprint "easyedapro:20K OHM RESISTOR (0603) SMD - CRCW060320K0FKEAC")
      (fields
        (field (name "Manufacturer Part") "71-CRCW060320K0FKEAC")
        (field (name "Manufacturer") "Vishay/Dale")
      )
      (libsource (lib "easyedapro") (part "."))
    )
    (comp (ref "R62")
      (value ".")
      (footprint "easyedapro:20K OHM RESISTOR (0603) SMD - CRCW060320K0FKEAC")
      (fields
        (field (name "Manufacturer Part") "71-CRCW060320K0FKEAC")
        (field (name "Manufacturer") "Vishay/Dale")
      )
      (libsource (lib "easyedapro") (part "."))
    )
    (comp (ref "R63")
      (value ".")
      (footprint "easyedapro:20K OHM RESISTOR (0603) SMD - CRCW060320K0FKEAC")
      (fields
        (field (name "Manufacturer Part") "71-CRCW060320K0FKEAC")
        (field (name "Manufacturer") "Vishay/Dale")
      )
      (libsource (lib "easyedapro") (part "."))
    )
    (comp (ref "TP6")
      (value "TP_ECG")
      (footprint "easyedapro:TESTPOINT")
      (libsource (lib "easyedapro") (part "TP_ECG"))
    )
    (comp (ref "TP7")
      (value "TP_LA")
      (footprint "easyedapro:TESTPOINT")
      (libsource (lib "easyedapro") (part "TP_LA"))
    )
    (comp (ref "TP8")
      (value "TP_RA")
      (footprint "easyedapro:TESTPOINT")
      (libsource (lib "easyedapro") (part "TP_RA"))
    )
    (comp (ref "TP9")
      (value "TP_RL")
      (footprint "easyedapro:TESTPOINT")
      (libsource (lib "easyedapro") (part "TP_RL"))
    )
    (comp (ref "U3")
      (value "AD8232ACPZ-R7")
      (footprint "easyedapro:LFCSP-20_L4.0-W4.0-P0.50-TL-EP2.7")
      (fields (field (name "Manufacturer") "ADI(亚德诺)"))
      (libsource (lib "easyedapro") (part "AD8232ACPZ-R7"))
    )
    (comp (ref "C10")
      (value "100nF")
      (footprint "easyedapro:C0603")
      (fields (field (name "Manufacturer Part") "0603F104Z500CT") (field (name "Manufacturer") "Walsin(华新科)"))
      (libsource (lib "easyedapro") (part "100nF"))
    )
    (comp (ref "C11")
      (value "100nF")
      (footprint "easyedapro:C0603")
      (fields (field (name "Manufacturer Part") "0603F104Z500CT") (field (name "Manufacturer") "Walsin(华新科)"))
      (libsource (lib "easyedapro") (part "100nF"))
    )
    (comp (ref "C12")
      (value "100nF")
      (footprint "easyedapro:C0603")
      (fields (field (name "Manufacturer Part") "0603F104Z500CT") (field (name "Manufacturer") "Walsin(华新科)"))
      (libsource (lib "easyedapro") (part "100nF"))
    )
    (comp (ref "C13")
      (value "100nF")
      (footprint "easyedapro:C0603")
      (fields (field (name "Manufacturer Part") "0603F104Z500CT") (field (name "Manufacturer") "Walsin(华新科)"))
      (libsource (lib "easyedapro") (part "100nF"))
    )
    (comp (ref "CN2")
      (value "PICO USB SIGNAL")
      (footprint "easyedapro:CONN-TH_KF2510-2A")
      (fields (field (name "Manufacturer Part") "外接电机-KF2510直针 两个针间距2.54mm"))
      (libsource (lib "easyedapro") (part "PICO USB SIGNAL"))
    )
    (comp (ref "PWR1")
      (value "TBA 2-1211")
      (footprint "easyedapro:PWRM-TH_TBA-2-1211")
      (fields (field (name "Manufacturer") "TRACO POWER"))
      (libsource (lib "easyedapro") (part "TBA 2-1211"))
    )
    (comp (ref "R16")
      (value ".")
      (footprint "easyedapro:20K OHM RESISTOR (0603) SMD - CRCW060320K0FKEAC")
      (fields
        (field (name "Manufacturer Part") "71-CRCW060320K0FKEAC")
        (field (name "Manufacturer") "Vishay/Dale")
      )
      (libsource (lib "easyedapro") (part "."))
    )
    (comp (ref "R17")
      (value ".")
      (footprint "easyedapro:20K OHM RESISTOR (0603) SMD - CRCW060320K0FKEAC")
      (fields
        (field (name "Manufacturer Part") "71-CRCW060320K0FKEAC")
        (field (name "Manufacturer") "Vishay/Dale")
      )
      (libsource (lib "easyedapro") (part "."))
    )
    (comp (ref "R18")
      (value ".")
      (footprint "easyedapro:20K OHM RESISTOR (0603) SMD - CRCW060320K0FKEAC")
      (fields
        (field (name "Manufacturer Part") "71-CRCW060320K0FKEAC")
        (field (name "Manufacturer") "Vishay/Dale")
      )
      (libsource (lib "easyedapro") (part "."))
    )
    (comp (ref "R19")
      (value ".")
      (footprint "easyedapro:20K OHM RESISTOR (0603) SMD - CRCW060320K0FKEAC")
      (fields
        (field (name "Manufacturer Part") "71-CRCW060320K0FKEAC")
        (field (name "Manufacturer") "Vishay/Dale")
      )
      (libsource (lib "easyedapro") (part "."))
    )
    (comp (ref "U4")
      (value "ADUM3160BRWZ-RL")
      (footprint "easyedapro:SOIC-16_L10.3-W7.5-P1.27-LS10.3-BL")
      (fields (field (name "Manufacturer") "ADI(亚德诺)"))
      (libsource (lib "easyedapro") (part "ADUM3160BRWZ-RL"))
    )
    (comp (ref "USB1")
      (value "670688000")
      (footprint "easyedapro:USB-B-TH_67068-8000")
      (fields (field (name "Manufacturer") "MOLEX"))
      (libsource (lib "easyedapro") (part "670688000"))
    )
    (comp (ref "BUZZER1")
      (value "BUZZER-12X9")
      (footprint "easyedapro:BUZ-TH_BD12.0-P7.60-D0.6-FD")
      (fields (field (name "Manufacturer Part") "buzzer-12X9"))
      (libsource (lib "easyedapro") (part "BUZZER-12X9"))
    )
    (comp (ref "C21")
      (value "100nF")
      (footprint "easyedapro:C0603")
      (fields (field (name "Manufacturer Part") "0603F104Z500CT") (field (name "Manufacturer") "Walsin(华新科)"))
      (libsource (lib "easyedapro") (part "100nF"))
    )
    (comp (ref "CN13")
      (value "LED_CONN")
      (footprint "easyedapro:CONN-TH_3P-P2.00_KF2510_3A")
      (fields (field (name "Manufacturer Part") "2510-3A") (field (name "Manufacturer") "BOOMELE(博穆精密)"))
      (libsource (lib "easyedapro") (part "LED_CONN"))
    )
    (comp (ref "CN14")
      (value "BUZZER")
      (footprint "easyedapro:CONN-TH_KF2510-2A")
      (fields (field (name "Manufacturer Part") "外接电机-KF2510直针 两个针间距2.54mm"))
      (libsource (lib "easyedapro") (part "BUZZER"))
    )
    (comp (ref "MH1")
      (value "M3 Screw")
      (footprint "easyedapro:MOUNTINGHOLE-M3")
      (libsource (lib "easyedapro") (part "M3 Screw"))
    )
    (comp (ref "MH2")
      (value "M3 Screw")
      (footprint "easyedapro:MOUNTINGHOLE-M3")
      (libsource (lib "easyedapro") (part "M3 Screw"))
    )
    (comp (ref "MH3")
      (value "M3 Screw")
      (footprint "easyedapro:MOUNTINGHOLE-M3")
      (libsource (lib "easyedapro") (part "M3 Screw"))
    )
    (comp (ref "MH4")
      (value "M3 Screw")
      (footprint "easyedapro:MOUNTINGHOLE-M3")
      (libsource (lib "easyedapro") (part "M3 Screw"))
    )
    (comp (ref "P4")
      (value "Encoder")
      (footprint "easyedapro:CONN-TH_5P-P2.54_KF2510-5A")
      (fields (field (name "Manufacturer Part") "2510-5A") (field (name "Manufacturer") "BOOMELE(博穆精密)"))
      (libsource (lib "easyedapro") (part "Encoder"))
    )
    (comp (ref "P5")
      (value "KF2510-4A")
      (footprint "easyedapro:CONN-TH_4P-P2.54_KF2510-4A")
      (fields (field (name "Manufacturer") "ReliaPro"))
      (libsource (lib "easyedapro") (part "KF2510-4A"))
    )
    (comp (ref "P6")
      (value "KF2510-4A")
      (footprint "easyedapro:CONN-TH_4P-P2.54_KF2510-4A")
      (fields (field (name "Manufacturer") "ReliaPro"))
      (libsource (lib "easyedapro") (part "KF2510-4A"))
    )
    (comp (ref "P7")
      (value "KF2510-4A")
      (footprint "easyedapro:CONN-TH_4P-P2.54_KF2510-4A")
      (fields (field (name "Manufacturer") "ReliaPro"))
      (libsource (lib "easyedapro") (part "KF2510-4A"))
    )
    (comp (ref "P9")
      (value "I2C PU")
      (footprint "easyedapro:2X2X2.54MM HEADER")
      (fields
        (field (name "Manufacturer Part") "Header-Female-2.54_1x4")
        (field (name "Manufacturer") "ReliaPro")
      )
      (libsource (lib "easyedapro") (part "I2C PU"))
    )
    (comp (ref "P10")
      (value "I2C PU")
      (footprint "easyedapro:2X2X2.54MM HEADER")
      (fields
        (field (name "Manufacturer Part") "Header-Female-2.54_1x4")
        (field (name "Manufacturer") "ReliaPro")
      )
      (libsource (lib "easyedapro") (part "I2C PU"))
    )
    (comp (ref "P12")
      (value "KF2510-4A")
      (footprint "easyedapro:CONN-TH_4P-P2.54_KF2510-4A")
      (fields (field (name "Manufacturer") "ReliaPro"))
      (libsource (lib "easyedapro") (part "KF2510-4A"))
    )
    (comp (ref "P13")
      (value "KF2510-4A")
      (footprint "easyedapro:CONN-TH_4P-P2.54_KF2510-4A")
      (fields (field (name "Manufacturer") "ReliaPro"))
      (libsource (lib "easyedapro") (part "KF2510-4A"))
    )
    (comp (ref "P14")
      (value "KF2510-4A")
      (footprint "easyedapro:CONN-TH_4P-P2.54_KF2510-4A")
      (fields (field (name "Manufacturer") "ReliaPro"))
      (libsource (lib "easyedapro") (part "KF2510-4A"))
    )
    (comp (ref "Q1")
      (value "BSS138BKW")
      (footprint "easyedapro:SOT323")
      (libsource (lib "easyedapro") (part "BSS138BKW"))
    )
    (comp (ref "R15")
      (value ".")
      (footprint "easyedapro:20K OHM RESISTOR (0603) SMD - CRCW060320K0FKEAC")
      (fields
        (field (name "Manufacturer Part") "71-CRCW060320K0FKEAC")
        (field (name "Manufacturer") "Vishay/Dale")
      )
      (libsource (lib "easyedapro") (part "."))
    )
    (comp (ref "R56")
      (value ".")
      (footprint "easyedapro:20K OHM RESISTOR (0603) SMD - CRCW060320K0FKEAC")
      (fields
        (field (name "Manufacturer Part") "71-CRCW060320K0FKEAC")
        (field (name "Manufacturer") "Vishay/Dale")
      )
      (libsource (lib "easyedapro") (part "."))
    )
    (comp (ref "R57")
      (value ".")
      (footprint "easyedapro:20K OHM RESISTOR (0603) SMD - CRCW060320K0FKEAC")
      (fields
        (field (name "Manufacturer Part") "71-CRCW060320K0FKEAC")
        (field (name "Manufacturer") "Vishay/Dale")
      )
      (libsource (lib "easyedapro") (part "."))
    )
    (comp (ref "R58")
      (value ".")
      (footprint "easyedapro:20K OHM RESISTOR (0603) SMD - CRCW060320K0FKEAC")
      (fields
        (field (name "Manufacturer Part") "71-CRCW060320K0FKEAC")
        (field (name "Manufacturer") "Vishay/Dale")
      )
      (libsource (lib "easyedapro") (part "."))
    )
    (comp (ref "R59")
      (value ".")
      (footprint "easyedapro:20K OHM RESISTOR (0603) SMD - CRCW060320K0FKEAC")
      (fields
        (field (name "Manufacturer Part") "71-CRCW060320K0FKEAC")
        (field (name "Manufacturer") "Vishay/Dale")
      )
      (libsource (lib "easyedapro") (part "."))
    )
    (comp (ref "R60")
      (value ".")
      (footprint "easyedapro:20K OHM RESISTOR (0603) SMD - CRCW060320K0FKEAC")
      (fields
        (field (name "Manufacturer Part") "71-CRCW060320K0FKEAC")
        (field (name "Manufacturer") "Vishay/Dale")
      )
      (libsource (lib "easyedapro") (part "."))
    )
    (comp (ref "U5")
      (value "Raspberry Pi Pico")
      (footprint "easyedapro:RASPBERRY PI PICO/ RASPBERRY PI PICO W")
      (libsource (lib "easyedapro") (part "Raspberry Pi Pico"))
    )
    (comp (ref "C23")
      (value "10uF")
      (footprint "easyedapro:C0805")
      (fields
        (field (name "Manufacturer Part") "C0805C106K4PAC7210")
        (field (name "Manufacturer") "KEMET(基美)")
      )
      (libsource (lib "easyedapro") (part "10uF"))
    )
    (comp (ref "C26")
      (value "100nF")
      (footprint "easyedapro:C0603")
      (fields (field (name "Manufacturer Part") "0603F104Z500CT") (field (name "Manufacturer") "Walsin(华新科)"))
      (libsource (lib "easyedapro") (part "100nF"))
    )
    (comp (ref "C31")
      (value "10uF")
      (footprint "easyedapro:C0805")
      (fields
        (field (name "Manufacturer Part") "C0805C106K4PAC7210")
        (field (name "Manufacturer") "KEMET(基美)")
      )
      (libsource (lib "easyedapro") (part "10uF"))
    )
    (comp (ref "C32")
      (value "10uF")
      (footprint "easyedapro:C0805")
      (fields
        (field (name "Manufacturer Part") "C0805C106K4PAC7210")
        (field (name "Manufacturer") "KEMET(基美)")
      )
      (libsource (lib "easyedapro") (part "10uF"))
    )
    (comp (ref "C33")
      (value "50nF")
      (footprint "easyedapro:C0603")
      (fields (field (name "Manufacturer Part") "0603F104Z500CT") (field (name "Manufacturer") "Walsin(华新科)"))
      (libsource (lib "easyedapro") (part "50nF"))
    )
    (comp (ref "C34")
      (value "250uF")
      (footprint "easyedapro:8X10.5")
      (libsource (lib "easyedapro") (part "250uF"))
    )
    (comp (ref "C35")
      (value "100nF")
      (footprint "easyedapro:C0603")
      (fields (field (name "Manufacturer Part") "0603F104Z500CT") (field (name "Manufacturer") "Walsin(华新科)"))
      (libsource (lib "easyedapro") (part "100nF"))
    )
    (comp (ref "C36")
      (value "100nF")
      (footprint "easyedapro:C0603")
      (fields (field (name "Manufacturer Part") "0603F104Z500CT") (field (name "Manufacturer") "Walsin(华新科)"))
      (libsource (lib "easyedapro") (part "100nF"))
    )
    (comp (ref "C39")
      (value "100nF")
      (footprint "easyedapro:C0603")
      (fields (field (name "Manufacturer Part") "0603F104Z500CT") (field (name "Manufacturer") "Walsin(华新科)"))
      (libsource (lib "easyedapro") (part "100nF"))
    )
    (comp (ref "CN3")
      (value "kf2510_3A")
      (footprint "easyedapro:CONN-TH_3P-P2.00_KF2510_3A")
      (fields (field (name "Manufacturer Part") "2510-3A") (field (name "Manufacturer") "BOOMELE(博穆精密)"))
      (libsource (lib "easyedapro") (part "kf2510_3A"))
    )
    (comp (ref "CN5")
      (value "Speaker")
      (footprint "easyedapro:CONN-TH_KF2510-2A")
      (fields (field (name "Manufacturer Part") "外接电机-KF2510直针 两个针间距2.54mm"))
      (libsource (lib "easyedapro") (part "Speaker"))
    )
    (comp (ref "D3")
      (value "BAR43SFILM")
      (footprint "easyedapro:SOT-23_L2.9-W1.3-P1.90-LS2.4-BR")
      (fields (field (name "Manufacturer") "ST(意法半导体)"))
      (libsource (lib "easyedapro") (part "BAR43SFILM"))
    )
    (comp (ref "D4")
      (value "BAR43SFILM")
      (footprint "easyedapro:SOT-23_L2.9-W1.3-P1.90-LS2.4-BR")
      (fields (field (name "Manufacturer") "ST(意法半导体)"))
      (libsource (lib "easyedapro") (part "BAR43SFILM"))
    )
    (comp (ref "D6")
      (value "BAR43SFILM")
      (footprint "easyedapro:SOT-23_L2.9-W1.3-P1.90-LS2.4-BR")
      (fields (field (name "Manufacturer") "ST(意法半导体)"))
      (libsource (lib "easyedapro") (part "BAR43SFILM"))
    )
    (comp (ref "D8")
      (value "BAR43SFILM")
      (footprint "easyedapro:SOT-23_L2.9-W1.3-P1.90-LS2.4-BR")
      (fields (field (name "Manufacturer") "ST(意法半导体)"))
      (libsource (lib "easyedapro") (part "BAR43SFILM"))
    )
    (comp (ref "P1")
      (value "INA125 JMPR BLOCK")
      (footprint "easyedapro:2X2X2.54MM HEADER")
      (fields
        (field (name "Manufacturer Part") "Header-Female-2.54_1x4")
        (field (name "Manufacturer") "ReliaPro")
      )
      (libsource (lib "easyedapro") (part "INA125 JMPR BLOCK"))
    )
    (comp (ref "P2")
      (value "SPEAKER JMP")
      (footprint "easyedapro:2X2X2.54MM HEADER")
      (fields
        (field (name "Manufacturer Part") "Header-Female-2.54_1x4")
        (field (name "Manufacturer") "ReliaPro")
      )
      (libsource (lib "easyedapro") (part "SPEAKER JMP"))
    )
    (comp (ref "R20")
      (value ".")
      (footprint "easyedapro:20K OHM RESISTOR (0603) SMD - CRCW060320K0FKEAC")
      (fields
        (field (name "Manufacturer Part") "71-CRCW060320K0FKEAC")
        (field (name "Manufacturer") "Vishay/Dale")
      )
      (libsource (lib "easyedapro") (part "."))
    )
    (comp (ref "R21")
      (value ".")
      (footprint "easyedapro:20K OHM RESISTOR (0603) SMD - CRCW060320K0FKEAC")
      (fields
        (field (name "Manufacturer Part") "71-CRCW060320K0FKEAC")
        (field (name "Manufacturer") "Vishay/Dale")
      )
      (libsource (lib "easyedapro") (part "."))
    )
    (comp (ref "R22")
      (value ".")
      (footprint "easyedapro:20K OHM RESISTOR (0603) SMD - CRCW060320K0FKEAC")
      (fields
        (field (name "Manufacturer Part") "71-CRCW060320K0FKEAC")
        (field (name "Manufacturer") "Vishay/Dale")
      )
      (libsource (lib "easyedapro") (part "."))
    )
    (comp (ref "R23")
      (value ".")
      (footprint "easyedapro:20K OHM RESISTOR (0603) SMD - CRCW060320K0FKEAC")
      (fields
        (field (name "Manufacturer Part") "71-CRCW060320K0FKEAC")
        (field (name "Manufacturer") "Vishay/Dale")
      )
      (libsource (lib "easyedapro") (part "."))
    )
    (comp (ref "R24")
      (value ".")
      (footprint "easyedapro:20K OHM RESISTOR (0603) SMD - CRCW060320K0FKEAC")
      (fields
        (field (name "Manufacturer Part") "71-CRCW060320K0FKEAC")
        (field (name "Manufacturer") "Vishay/Dale")
      )
      (libsource (lib "easyedapro") (part "."))
    )
    (comp (ref "R25")
      (value ".")
      (footprint "easyedapro:20K OHM RESISTOR (0603) SMD - CRCW060320K0FKEAC")
      (fields
        (field (name "Manufacturer Part") "71-CRCW060320K0FKEAC")
        (field (name "Manufacturer") "Vishay/Dale")
      )
      (libsource (lib "easyedapro") (part "."))
    )
    (comp (ref "R39")
      (value ".")
      (footprint "easyedapro:20K OHM RESISTOR (0603) SMD - CRCW060320K0FKEAC")
      (fields
        (field (name "Manufacturer Part") "71-CRCW060320K0FKEAC")
        (field (name "Manufacturer") "Vishay/Dale")
      )
      (libsource (lib "easyedapro") (part "."))
    )
    (comp (ref "R40")
      (value ".")
      (footprint "easyedapro:20K OHM RESISTOR (0603) SMD - CRCW060320K0FKEAC")
      (fields
        (field (name "Manufacturer Part") "71-CRCW060320K0FKEAC")
        (field (name "Manufacturer") "Vishay/Dale")
      )
      (libsource (lib "easyedapro") (part "."))
    )
    (comp (ref "R41")
      (value ".")
      (footprint "easyedapro:20K OHM RESISTOR (0603) SMD - CRCW060320K0FKEAC")
      (fields
        (field (name "Manufacturer Part") "71-CRCW060320K0FKEAC")
        (field (name "Manufacturer") "Vishay/Dale")
      )
      (libsource (lib "easyedapro") (part "."))
    )
    (comp (ref "R42")
      (value "10k")
      (footprint "easyedapro:RES-ADJ-TH_3P-L9.5-W4.85-P2.50-BL-BS")
      (fields (field (name "Manufacturer Part") "3296W-1-502") (field (name "Manufacturer") "BOCHEN(博晨)"))
      (libsource (lib "easyedapro") (part "10k"))
    )
    (comp (ref "R43")
      (value "10k")
      (footprint "easyedapro:RES-ADJ-TH_3P-L9.5-W4.85-P2.50-BL-BS")
      (fields (field (name "Manufacturer Part") "3296W-1-502") (field (name "Manufacturer") "BOCHEN(博晨)"))
      (libsource (lib "easyedapro") (part "10k"))
    )
    (comp (ref "R44")
      (value ".")
      (footprint "easyedapro:20K OHM RESISTOR (0603) SMD - CRCW060320K0FKEAC")
      (fields
        (field (name "Manufacturer Part") "71-CRCW060320K0FKEAC")
        (field (name "Manufacturer") "Vishay/Dale")
      )
      (libsource (lib "easyedapro") (part "."))
    )
    (comp (ref "R45")
      (value "8R2/1206")
      (footprint "easyedapro:R1206")
      (fields (field (name "Manufacturer Part") "220K/1206"))
      (libsource (lib "easyedapro") (part "8R2/1206"))
    )
    (comp (ref "R46")
      (value ".")
      (footprint "easyedapro:20K OHM RESISTOR (0603) SMD - CRCW060320K0FKEAC")
      (fields
        (field (name "Manufacturer Part") "71-CRCW060320K0FKEAC")
        (field (name "Manufacturer") "Vishay/Dale")
      )
      (libsource (lib "easyedapro") (part "."))
    )
    (comp (ref "R47")
      (value ".")
      (footprint "easyedapro:20K OHM RESISTOR (0603) SMD - CRCW060320K0FKEAC")
      (fields
        (field (name "Manufacturer Part") "71-CRCW060320K0FKEAC")
        (field (name "Manufacturer") "Vishay/Dale")
      )
      (libsource (lib "easyedapro") (part "."))
    )
    (comp (ref "R52")
      (value ".")
      (footprint "easyedapro:20K OHM RESISTOR (0603) SMD - CRCW060320K0FKEAC")
      (fields
        (field (name "Manufacturer Part") "71-CRCW060320K0FKEAC")
        (field (name "Manufacturer") "Vishay/Dale")
      )
      (libsource (lib "easyedapro") (part "."))
    )
    (comp (ref "R53")
      (value ".")
      (footprint "easyedapro:20K OHM RESISTOR (0603) SMD - CRCW060320K0FKEAC")
      (fields
        (field (name "Manufacturer Part") "71-CRCW060320K0FKEAC")
        (field (name "Manufacturer") "Vishay/Dale")
      )
      (libsource (lib "easyedapro") (part "."))
    )
    (comp (ref "S1")
      (value "1825058-7")
      (footprint "easyedapro:SW_1825058-7")
      (libsource (lib "easyedapro") (part "1825058-7"))
    )
    (comp (ref "TP10")
      (value "TP_AUX1")
      (footprint "easyedapro:TESTPOINT")
      (libsource (lib "easyedapro") (part "TP_AUX1"))
    )
    (comp (ref "TP11")
      (value "TP_AUX2")
      (footprint "easyedapro:TESTPOINT")
      (libsource (lib "easyedapro") (part "TP_AUX2"))
    )
    (comp (ref "TP12")
      (value "TP_AUX3")
      (footprint "easyedapro:TESTPOINT")
      (libsource (lib "easyedapro") (part "TP_AUX3"))
    )
    (comp (ref "U9")
      (value "XS3A4051PWJ")
      (footprint "easyedapro:TSSOP16_")
      (fields (field (name "Manufacturer") "NEXPERIA"))
      (libsource (lib "easyedapro") (part "XS3A4051PWJ"))
    )
    (comp (ref "U13")
      (value "LM386M-1/NOPB")
      (footprint "easyedapro:SOIC-8_L4.9-W3.9-P1.27-LS6.0-BL-2")
      (fields (field (name "Manufacturer") "TI(德州仪器)"))
      (libsource (lib "easyedapro") (part "LM386M-1/NOPB"))
    )
    (comp (ref "U14")
      (value "MCP6001T-I/OT")
      (footprint "easyedapro:SOT-23-5_L3.0-W1.7-P0.95-LS2.8-BR")
      (fields (field (name "Manufacturer") "MICROCHIP(美国微芯)"))
      (libsource (lib "easyedapro") (part "MCP6001T-I/OT"))
    )
    (comp (ref "C1")
      (value "10uF")
      (footprint "easyedapro:C0805")
      (fields
        (field (name "Manufacturer Part") "C0805C106K4PAC7210")
        (field (name "Manufacturer") "KEMET(基美)")
      )
      (libsource (lib "easyedapro") (part "10uF"))
    )
    (comp (ref "C2")
      (value "10uF")
      (footprint "easyedapro:C0805")
      (fields
        (field (name "Manufacturer Part") "C0805C106K4PAC7210")
        (field (name "Manufacturer") "KEMET(基美)")
      )
      (libsource (lib "easyedapro") (part "10uF"))
    )
    (comp (ref "C25")
      (value "1.1nF")
      (footprint "easyedapro:C0603")
      (fields (field (name "Manufacturer Part") "0603F104Z500CT") (field (name "Manufacturer") "Walsin(华新科)"))
      (libsource (lib "easyedapro") (part "1.1nF"))
    )
    (comp (ref "C27")
      (value "22uF")
      (footprint "easyedapro:C0805")
      (fields (field (name "Manufacturer Part") "C0805C226M9PACTU") (field (name "Manufacturer") "KEMET(基美)"))
      (libsource (lib "easyedapro") (part "22uF"))
    )
    (comp (ref "C28")
      (value "22uF")
      (footprint "easyedapro:C0805")
      (fields (field (name "Manufacturer Part") "C0805C226M9PACTU") (field (name "Manufacturer") "KEMET(基美)"))
      (libsource (lib "easyedapro") (part "22uF"))
    )
    (comp (ref "C29")
      (value "1uF")
      (footprint "easyedapro:C0805")
      (fields (field (name "Manufacturer Part") "C0805C226M9PACTU") (field (name "Manufacturer") "KEMET(基美)"))
      (libsource (lib "easyedapro") (part "1uF"))
    )
    (comp (ref "C30")
      (value "100nF")
      (footprint "easyedapro:C0603")
      (fields (field (name "Manufacturer Part") "0603F104Z500CT") (field (name "Manufacturer") "Walsin(华新科)"))
      (libsource (lib "easyedapro") (part "100nF"))
    )
    (comp (ref "C37")
      (value "100nF")
      (footprint "easyedapro:C0603")
      (fields (field (name "Manufacturer Part") "0603F104Z500CT") (field (name "Manufacturer") "Walsin(华新科)"))
      (libsource (lib "easyedapro") (part "100nF"))
    )
    (comp (ref "C38")
      (value "100nF")
      (footprint "easyedapro:C0603")
      (fields (field (name "Manufacturer Part") "0603F104Z500CT") (field (name "Manufacturer") "Walsin(华新科)"))
      (libsource (lib "easyedapro") (part "100nF"))
    )
    (comp (ref "CN6")
      (value "BPM PSU")
      (footprint "easyedapro:CONN-TH_KF2510-2A")
      (fields (field (name "Manufacturer Part") "外接电机-KF2510直针 两个针间距2.54mm"))
      (libsource (lib "easyedapro") (part "BPM PSU"))
    )
    (comp (ref "CN7")
      (value "BPM BUTTON")
      (footprint "easyedapro:CONN-TH_KF2510-2A")
      (fields (field (name "Manufacturer Part") "外接电机-KF2510直针 两个针间距2.54mm"))
      (libsource (lib "easyedapro") (part "BPM BUTTON"))
    )
    (comp (ref "CN8")
      (value "BUTTON2")
      (footprint "easyedapro:CONN-TH_KF2510-2A")
      (fields (field (name "Manufacturer Part") "外接电机-KF2510直针 两个针间距2.54mm"))
      (libsource (lib "easyedapro") (part "BUTTON2"))
    )
    (comp (ref "CN9")
      (value "PUMP")
      (footprint "easyedapro:CONN-TH_KF2510-2A")
      (fields (field (name "Manufacturer Part") "外接电机-KF2510直针 两个针间距2.54mm"))
      (libsource (lib "easyedapro") (part "PUMP"))
    )
    (comp (ref "CN10")
      (value "VALVE")
      (footprint "easyedapro:CONN-TH_KF2510-2A")
      (fields (field (name "Manufacturer Part") "外接电机-KF2510直针 两个针间距2.54mm"))
      (libsource (lib "easyedapro") (part "VALVE"))
    )
    (comp (ref "D7")
      (value "RB050LAM-40TFTR")
      (footprint "easyedapro:SOD-128_L3.7-W2.5-LS4.7-RD")
      (fields (field (name "Manufacturer") "ROHM(罗姆)"))
      (libsource (lib "easyedapro") (part "RB050LAM-40TFTR"))
    )
    (comp (ref "D9")
      (value "BAR43SFILM")
      (footprint "easyedapro:SOT-23_L2.9-W1.3-P1.90-LS2.4-BR")
      (fields (field (name "Manufacturer") "ST(意法半导体)"))
      (libsource (lib "easyedapro") (part "BAR43SFILM"))
    )
    (comp (ref "L1")
      (value "MSS7341-104MLD")
      (footprint "easyedapro:IND-SMD_L7.3-W7.3_MSS7341-104MLD")
      (libsource (lib "easyedapro") (part "MSS7341-104MLD"))
    )
    (comp (ref "P3")
      (value "INA826_PWR_JMP")
      (footprint "easyedapro:2X2X2.54MM HEADER")
      (fields
        (field (name "Manufacturer Part") "Header-Female-2.54_1x4")
        (field (name "Manufacturer") "ReliaPro")
      )
      (libsource (lib "easyedapro") (part "INA826_PWR_JMP"))
    )
    (comp (ref "P15")
      (value "MPS_PWR_JMP")
      (footprint "easyedapro:2X2X2.54MM HEADER")
      (fields
        (field (name "Manufacturer Part") "Header-Female-2.54_1x4")
        (field (name "Manufacturer") "ReliaPro")
      )
      (libsource (lib "easyedapro") (part "MPS_PWR_JMP"))
    )
    (comp (ref "Q2")
      (value "DMN2310UW-7")
      (footprint "easyedapro:PG-SOT323-3_L2.0-W1.3-P1.30-LS2.1-BR")
      (fields (field (name "Manufacturer") "DiodesZetex"))
      (libsource (lib "easyedapro") (part "DMN2310UW-7"))
    )
    (comp (ref "Q3")
      (value "DMN2310UW-7")
      (footprint "easyedapro:PG-SOT323-3_L2.0-W1.3-P1.30-LS2.1-BR")
      (fields (field (name "Manufacturer") "DiodesZetex"))
      (libsource (lib "easyedapro") (part "DMN2310UW-7"))
    )
    (comp (ref "R26")
      (value ".")
      (footprint "easyedapro:20K OHM RESISTOR (0603) SMD - CRCW060320K0FKEAC")
      (fields
        (field (name "Manufacturer Part") "71-CRCW060320K0FKEAC")
        (field (name "Manufacturer") "Vishay/Dale")
      )
      (libsource (lib "easyedapro") (part "."))
    )
    (comp (ref "R27")
      (value ".")
      (footprint "easyedapro:20K OHM RESISTOR (0603) SMD - CRCW060320K0FKEAC")
      (fields
        (field (name "Manufacturer Part") "71-CRCW060320K0FKEAC")
        (field (name "Manufacturer") "Vishay/Dale")
      )
      (libsource (lib "easyedapro") (part "."))
    )
    (comp (ref "R38")
      (value ".")
      (footprint "easyedapro:20K OHM RESISTOR (0603) SMD - CRCW060320K0FKEAC")
      (fields
        (field (name "Manufacturer Part") "71-CRCW060320K0FKEAC")
        (field (name "Manufacturer") "Vishay/Dale")
      )
      (libsource (lib "easyedapro") (part "."))
    )
    (comp (ref "R48")
      (value "20Ω")
      (footprint "easyedapro:RES-ADJ-TH_3P-L9.5-W4.85-P2.50-BL-BS")
      (fields (field (name "Manufacturer Part") "3296W-1-502") (field (name "Manufacturer") "BOCHEN(博晨)"))
      (libsource (lib "easyedapro") (part "20Ω"))
    )
    (comp (ref "R49")
      (value ".")
      (footprint "easyedapro:20K OHM RESISTOR (0603) SMD - CRCW060320K0FKEAC")
      (fields
        (field (name "Manufacturer Part") "71-CRCW060320K0FKEAC")
        (field (name "Manufacturer") "Vishay/Dale")
      )
      (libsource (lib "easyedapro") (part "."))
    )
    (comp (ref "R50")
      (value ".")
      (footprint "easyedapro:20K OHM RESISTOR (0603) SMD - CRCW060320K0FKEAC")
      (fields
        (field (name "Manufacturer Part") "71-CRCW060320K0FKEAC")
        (field (name "Manufacturer") "Vishay/Dale")
      )
      (libsource (lib "easyedapro") (part "."))
    )
    (comp (ref "R51")
      (value ".")
      (footprint "easyedapro:20K OHM RESISTOR (0603) SMD - CRCW060320K0FKEAC")
      (fields
        (field (name "Manufacturer Part") "71-CRCW060320K0FKEAC")
        (field (name "Manufacturer") "Vishay/Dale")
      )
      (libsource (lib "easyedapro") (part "."))
    )
    (comp (ref "R54")
      (value ".")
      (footprint "easyedapro:20K OHM RESISTOR (0603) SMD - CRCW060320K0FKEAC")
      (fields
        (field (name "Manufacturer Part") "71-CRCW060320K0FKEAC")
        (field (name "Manufacturer") "Vishay/Dale")
      )
      (libsource (lib "easyedapro") (part "."))
    )
    (comp (ref "R55")
      (value ".")
      (footprint "easyedapro:20K OHM RESISTOR (0603) SMD - CRCW060320K0FKEAC")
      (fields
        (field (name "Manufacturer Part") "71-CRCW060320K0FKEAC")
        (field (name "Manufacturer") "Vishay/Dale")
      )
      (libsource (lib "easyedapro") (part "."))
    )
    (comp (ref "TP4")
      (value "Testpoint 6V")
      (footprint "easyedapro:TESTPOINT")
      (libsource (lib "easyedapro") (part "Testpoint 6V"))
    )
    (comp (ref "TP14")
      (value "TP_PRESSURE")
      (footprint "easyedapro:TESTPOINT")
      (libsource (lib "easyedapro") (part "TP_PRESSURE"))
    )
    (comp (ref "TP15")
      (value "MPS+")
      (footprint "easyedapro:TESTPOINT")
      (libsource (lib "easyedapro") (part "MPS+"))
    )
    (comp (ref "TP16")
      (value "MPS-")
      (footprint "easyedapro:TESTPOINT")
      (libsource (lib "easyedapro") (part "MPS-"))
    )
    (comp (ref "U6")
      (value "TPS61085PWR")
      (footprint "easyedapro:TSSOP-8_L4.4-W3.0-P0.65-LS6.4-BL")
      (fields (field (name "Manufacturer") "TI(德州仪器)"))
      (libsource (lib "easyedapro") (part "TPS61085PWR"))
    )
    (comp (ref "U15")
      (value "MPS20N0040D-S")
      (footprint "easyedapro:MPS20N0040D-S")
      (libsource (lib "easyedapro") (part "MPS20N0040D-S"))
    )
    (comp (ref "U16")
      (value "INA826AIDGK")
      (footprint "easyedapro:VSSOP-8_L3.0-W3.0-P0.65-LS4.9-BL")
      (fields (field (name "Manufacturer") "TI(德州仪器)"))
      (libsource (lib "easyedapro") (part "INA826AIDGK"))
    )
    (comp (ref "U17")
      (value "4N27M")
      (footprint "easyedapro:DIP-6_L8.8-W6.4-P2.54-LS7.6-BL")
      (fields (field (name "Manufacturer") "onsemi(安森美)"))
      (libsource (lib "easyedapro") (part "4N27M"))
    )
  )
  (nets
    (net (code "1") (name "3V3") (class "Default")
      (node (ref "C12") (pin "1") (pinfunction "1_1") (pintype "unspecified"))
      (node (ref "C13") (pin "1") (pinfunction "1_1") (pintype "unspecified"))
      (node (ref "C17") (pin "2") (pinfunction "2_2") (pintype "unspecified"))
      (node (ref "C18") (pin "2") (pinfunction "2_2") (pintype "unspecified"))
      (node (ref "C19") (pin "2") (pinfunction "2_2") (pintype "unspecified"))
      (node (ref "C21") (pin "1") (pinfunction "1_1") (pintype "unspecified"))
      (node (ref "C26") (pin "2") (pinfunction "2_2") (pintype "unspecified"))
      (node (ref "C9") (pin "2") (pinfunction "2_2") (pintype "unspecified"))
      (node (ref "CN4") (pin "2") (pinfunction "2_2") (pintype "unspecified"))
      (node (ref "D3") (pin "2") (pinfunction "2_2") (pintype "unspecified"))
      (node (ref "D6") (pin "2") (pinfunction "2_2") (pintype "unspecified"))
      (node (ref "D8") (pin "2") (pinfunction "2_2") (pintype "unspecified"))
      (node (ref "D9") (pin "2") (pinfunction "2_2") (pintype "unspecified"))
      (node (ref "P12") (pin "4") (pinfunction "4_4") (pintype "unspecified"))
      (node (ref "P13") (pin "4") (pinfunction "4_4") (pintype "unspecified"))
      (node (ref "P14") (pin "4") (pinfunction "4_4") (pintype "unspecified"))
      (node (ref "P15") (pin "2") (pinfunction "2_2") (pintype "input"))
      (node (ref "P3") (pin "2") (pinfunction "2_2") (pintype "input"))
      (node (ref "P4") (pin "5") (pinfunction "5_5") (pintype "unspecified"))
      (node (ref "P5") (pin "4") (pinfunction "4_4") (pintype "unspecified"))
      (node (ref "P6") (pin "4") (pinfunction "4_4") (pintype "unspecified"))
      (node (ref "P7") (pin "4") (pinfunction "4_4") (pintype "unspecified"))
      (node (ref "R13") (pin "1") (pinfunction "1_1") (pintype "unspecified"))
      (node (ref "R20") (pin "2") (pinfunction "2_2") (pintype "unspecified"))
      (node (ref "R3") (pin "2") (pinfunction "2_2") (pintype "unspecified"))
      (node (ref "R30") (pin "1") (pinfunction "1_1") (pintype "unspecified"))
      (node (ref "R4") (pin "2") (pinfunction "2_2") (pintype "unspecified"))
      (node (ref "R57") (pin "1") (pinfunction "1_1") (pintype "unspecified"))
      (node (ref "R58") (pin "1") (pinfunction "1_1") (pintype "unspecified"))
      (node (ref "R59") (pin "1") (pinfunction "1_1") (pintype "unspecified"))
      (node (ref "R60") (pin "1") (pinfunction "1_1") (pintype "unspecified"))
      (node (ref "TP1") (pin "1") (pinfunction "1_1") (pintype "unspecified"))
      (node (ref "U3") (pin "15") (pinfunction "FR_15") (pintype "unspecified"))
      (node (ref "U3") (pin "17") (pinfunction "+VS_17") (pintype "unspecified"))
      (node (ref "U4") (pin "12") (pinfunction "PIN_12") (pintype "unspecified"))
      (node (ref "U4") (pin "13") (pinfunction "SPD_13") (pintype "unspecified"))
      (node (ref "U4") (pin "14") (pinfunction "VDD2_14") (pintype "unspecified"))
      (node (ref "U4") (pin "16") (pinfunction "VBUS2_16") (pintype "unspecified"))
      (node (ref "U5") (pin "36") (pinfunction "3v3_(OUT)_36") (pintype "unspecified"))
      (node (ref "U7") (pin "3") (pinfunction "FB_3") (pintype "unspecified"))
      (node (ref "U7") (pin "4") (pinfunction "VOUT_4") (pintype "unspecified"))
      (node (ref "U7") (pin "5") (pinfunction "VOUT_5") (pintype "unspecified"))
      (node (ref "U9") (pin "16") (pinfunction "VCC_16") (pintype "unspecified"))
    )
    (net (code "2") (name "5V") (class "Default")
      (node (ref "BUZZER1") (pin "1") (pinfunction "+_1") (pintype "unspecified"))
      (node (ref "C42") (pin "2") (pinfunction "2_2") (pintype "unspecified"))
      (node (ref "CN13") (pin "3") (pinfunction "3_3") (pintype "unspecified"))
      (node (ref "CN14") (pin "2") (pinfunction "2_2") (pintype "unspecified"))
      (node (ref "U2") (pin "1") (pinfunction "OUT_1") (pintype "unspecified"))
    )
    (net (code "3") (name "5V_SAFE") (class "Default")
      (node (ref "C20") (pin "1") (pinfunction "1_1") (pintype "unspecified"))
      (node (ref "C22") (pin "1") (pinfunction "1_1") (pintype "unspecified"))
      (node (ref "PWR1") (pin "6") (pinfunction "+VOUT_6") (pintype "unspecified"))
      (node (ref "R33") (pin "2") (pinfunction "2_2") (pintype "unspecified"))
      (node (ref "TP13") (pin "1") (pinfunction "1_1") (pintype "unspecified"))
      (node (ref "U12") (pin "4") (pinfunction "VDD_4") (pintype "unspecified"))
    )
    (net (code "4") (name "5V_USB") (class "Default")
      (node (ref "C11") (pin "2") (pinfunction "2_2") (pintype "unspecified"))
      (node (ref "PWR1") (pin "1") (pinfunction "+VIN(VCC)_1") (pintype "unspecified"))
      (node (ref "U4") (pin "1") (pinfunction "VBUS1_1") (pintype "unspecified"))
      (node (ref "USB1") (pin "1") (pinfunction "VCC_1") (pintype "unspecified"))
    )
    (net (code "5") (name "6V") (class "Default")
      (node (ref "C1") (pin "1") (pinfunction "1_1") (pintype "unspecified"))
      (node (ref "C2") (pin "1") (pinfunction "1_1") (pintype "unspecified"))
      (node (ref "C28") (pin "1") (pinfunction "1_1") (pintype "unspecified"))
      (node (ref "C35") (pin "1") (pinfunction "1_1") (pintype "unspecified"))
      (node (ref "C36") (pin "1") (pinfunction "1_1") (pintype "unspecified"))
      (node (ref "C43") (pin "2") (pinfunction "2_2") (pintype "unspecified"))
      (node (ref "CN10") (pin "1") (pinfunction "1_1") (pintype "unspecified"))
      (node (ref "CN6") (pin "1") (pinfunction "1_1") (pintype "unspecified"))
      (node (ref "CN9") (pin "1") (pinfunction "1_1") (pintype "unspecified"))
      (node (ref "D7") (pin "1") (pinfunction "-_1") (pintype "unspecified"))
      (node (ref "P15") (pin "1") (pinfunction "1_1") (pintype "input"))
      (node (ref "P3") (pin "1") (pinfunction "1_1") (pintype "input"))
      (node (ref "R27") (pin "2") (pinfunction "2_2") (pintype "unspecified"))
      (node (ref "TP4") (pin "1") (pinfunction "1_1") (pintype "unspecified"))
      (node (ref "U13") (pin "6") (pinfunction "VS_6") (pintype "unspecified"))
      (node (ref "U14") (pin "5") (pinfunction "VDD_5") (pintype "unspecified"))
      (node (ref "U2") (pin "3") (pinfunction "IN_3") (pintype "unspecified"))
    )
    (net (code "6") (name "AUX1") (class "Default")
      (node (ref "C23") (pin "1") (pinfunction "1_1") (pintype "unspecified"))
      (node (ref "D3") (pin "3") (pinfunction "3_3") (pintype "unspecified"))
      (node (ref "R20") (pin "1") (pinfunction "1_1") (pintype "unspecified"))
      (node (ref "R21") (pin "2") (pinfunction "2_2") (pintype "unspecified"))
      (node (ref "S1") (pin "1") (pinfunction "1_1") (pintype "unspecified"))
      (node (ref "TP10") (pin "1") (pinfunction "1_1") (pintype "unspecified"))
    )
    (net (code "7") (name "AUX2") (class "Default")
      (node (ref "D6") (pin "3") (pinfunction "3_3") (pintype "unspecified"))
      (node (ref "R22") (pin "1") (pinfunction "1_1") (pintype "unspecified"))
      (node (ref "R23") (pin "2") (pinfunction "2_2") (pintype "unspecified"))
      (node (ref "S1") (pin "3") (pinfunction "3_3") (pintype "unspecified"))
      (node (ref "TP11") (pin "1") (pinfunction "1_1") (pintype "unspecified"))
    )
    (net (code "8") (name "AUX3") (class "Default")
      (node (ref "R46") (pin "1") (pinfunction "1_1") (pintype "unspecified"))
      (node (ref "R47") (pin "2") (pinfunction "2_2") (pintype "unspecified"))
      (node (ref "S1") (pin "5") (pinfunction "5_5") (pintype "unspecified"))
      (node (ref "TP12") (pin "1") (pinfunction "1_1") (pintype "unspecified"))
    )
    (net (code "9") (name "AUX_SIG") (class "Default")
      (node (ref "D4") (pin "1") (pinfunction "1_1") (pintype "unspecified"))
      (node (ref "P1") (pin "3") (pinfunction "3_3") (pintype "input"))
      (node (ref "P1") (pin "4") (pinfunction "4_4") (pintype "input"))
      (node (ref "R24") (pin "2") (pinfunction "2_2") (pintype "unspecified"))
      (node (ref "R42") (pin "3") (pinfunction "3_3") (pintype "unspecified"))
    )
    (net (code "10") (name "BAT") (class "Default")
      (node (ref "C39") (pin "1") (pinfunction "1_1") (pintype "unspecified"))
      (node (ref "R52") (pin "2") (pinfunction "2_2") (pintype "unspecified"))
      (node (ref "R53") (pin "1") (pinfunction "1_1") (pintype "unspecified"))
      (node (ref "S1") (pin "7") (pinfunction "7_7") (pintype "unspecified"))
    )
    (net (code "11") (name "BUTTON_SIG") (class "Default")
      (node (ref "R64") (pin "1") (pinfunction "1_1") (pintype "unspecified"))
      (node (ref "R65") (pin "2") (pinfunction "2_2") (pintype "unspecified"))
      (node (ref "U5") (pin "4") (pinfunction "GPIO_2_4") (pintype "unspecified"))
    )
    (net (code "12") (name "GND") (class "Default")
      (node (ref "C1") (pin "2") (pinfunction "2_2") (pintype "unspecified"))
      (node (ref "C12") (pin "2") (pinfunction "2_2") (pintype "unspecified"))
      (node (ref "C13") (pin "2") (pinfunction "2_2") (pintype "unspecified"))
      (node (ref "C14") (pin "2") (pinfunction "2_2") (pintype "unspecified"))
      (node (ref "C15") (pin "1") (pinfunction "1_1") (pintype "unspecified"))
      (node (ref "C16") (pin "1") (pinfunction "1_1") (pintype "unspecified"))
      (node (ref "C17") (pin "1") (pinfunction "1_1") (pintype "unspecified"))
      (node (ref "C18") (pin "1") (pinfunction "1_1") (pintype "unspecified"))
      (node (ref "C19") (pin "1") (pinfunction "1_1") (pintype "unspecified"))
      (node (ref "C2") (pin "2") (pinfunction "2_2") (pintype "unspecified"))
      (node (ref "C20") (pin "2") (pinfunction "2_2") (pintype "unspecified"))
      (node (ref "C21") (pin "2") (pinfunction "2_2") (pintype "unspecified"))
      (node (ref "C22") (pin "2") (pinfunction "2_2") (pintype "unspecified"))
      (node (ref "C25") (pin "1") (pinfunction "1_1") (pintype "unspecified"))
      (node (ref "C26") (pin "1") (pinfunction "1_1") (pintype "unspecified"))
      (node (ref "C27") (pin "2") (pinfunction "2_2") (pintype "unspecified"))
      (node (ref "C28") (pin "2") (pinfunction "2_2") (pintype "unspecified"))
      (node (ref "C29") (pin "2") (pinfunction "2_2") (pintype "unspecified"))
      (node (ref "C30") (pin "1") (pinfunction "1_1") (pintype "unspecified"))
      (node (ref "C32") (pin "1") (pinfunction "1_1") (pintype "unspecified"))
      (node (ref "C33") (pin "2") (pinfunction "2_2") (pintype "unspecified"))
      (node (ref "C35") (pin "2") (pinfunction "2_2") (pintype "unspecified"))
      (node (ref "C36") (pin "2") (pinfunction "2_2") (pintype "unspecified"))
      (node (ref "C37") (pin "1") (pinfunction "1_1") (pintype "unspecified"))
      (node (ref "C38") (pin "2") (pinfunction "2_2") (pintype "unspecified"))
      (node (ref "C39") (pin "2") (pinfunction "2_2") (pintype "unspecified"))
      (node (ref "C42") (pin "1") (pinfunction "1_1") (pintype "unspecified"))
      (node (ref "C43") (pin "1") (pinfunction "1_1") (pintype "unspecified"))
      (node (ref "C8") (pin "1") (pinfunction "1_1") (pintype "unspecified"))
      (node (ref "C9") (pin "1") (pinfunction "1_1") (pintype "unspecified"))
      (node (ref "CN13") (pin "1") (pinfunction "1_1") (pintype "unspecified"))
      (node (ref "CN3") (pin "1") (pinfunction "1_1") (pintype "unspecified"))
      (node (ref "CN4") (pin "1") (pinfunction "1_1") (pintype "unspecified"))
      (node (ref "CN5") (pin "2") (pinfunction "2_2") (pintype "unspecified"))
      (node (ref "CN6") (pin "2") (pinfunction "2_2") (pintype "unspecified"))
      (node (ref "D3") (pin "1") (pinfunction "1_1") (pintype "unspecified"))
      (node (ref "D6") (pin "1") (pinfunction "1_1") (pintype "unspecified"))
      (node (ref "D8") (pin "1") (pinfunction "1_1") (pintype "unspecified"))
      (node (ref "D9") (pin "1") (pinfunction "1_1") (pintype "unspecified"))
      (node (ref "P12") (pin "1") (pinfunction "1_1") (pintype "unspecified"))
      (node (ref "P13") (pin "1") (pinfunction "1_1") (pintype "unspecified"))
      (node (ref "P14") (pin "1") (pinfunction "1_1") (pintype "unspecified"))
      (node (ref "P4") (pin "4") (pinfunction "4_4") (pintype "unspecified"))
      (node (ref "P5") (pin "1") (pinfunction "1_1") (pintype "unspecified"))
      (node (ref "P6") (pin "1") (pinfunction "1_1") (pintype "unspecified"))
      (node (ref "P7") (pin "1") (pinfunction "1_1") (pintype "unspecified"))
      (node (ref "PWR1") (pin "4") (pinfunction "-VOUT_4") (pintype "unspecified"))
      (node (ref "Q1") (pin "2") (pinfunction "S_2") (pintype "bidirectional"))
      (node (ref "Q2") (pin "2") (pinfunction "S_2") (pintype "unspecified"))
      (node (ref "Q3") (pin "2") (pinfunction "S_2") (pintype "unspecified"))
      (node (ref "Q6") (pin "3") (pinfunction "D_3") (pintype "bidirectional"))
      (node (ref "R14") (pin "2") (pinfunction "2_2") (pintype "unspecified"))
      (node (ref "R21") (pin "1") (pinfunction "1_1") (pintype "unspecified"))
      (node (ref "R23") (pin "1") (pinfunction "1_1") (pintype "unspecified"))
      (node (ref "R25") (pin "1") (pinfunction "1_1") (pintype "unspecified"))
      (node (ref "R26") (pin "1") (pinfunction "1_1") (pintype "unspecified"))
      (node (ref "R29") (pin "2") (pinfunction "2_2") (pintype "unspecified"))
      (node (ref "R31") (pin "1") (pinfunction "1_1") (pintype "unspecified"))
      (node (ref "R32") (pin "1") (pinfunction "1_1") (pintype "unspecified"))
      (node (ref "R35") (pin "1") (pinfunction "1_1") (pintype "unspecified"))
      (node (ref "R36") (pin "1") (pinfunction "1_1") (pintype "unspecified"))
      (node (ref "R37") (pin "1") (pinfunction "1_1") (pintype "unspecified"))
      (node (ref "R39") (pin "1") (pinfunction "1_1") (pintype "unspecified"))
      (node (ref "R40") (pin "1") (pinfunction "1_1") (pintype "unspecified"))
      (node (ref "R41") (pin "1") (pinfunction "1_1") (pintype "unspecified"))
      (node (ref "R42") (pin "1") (pinfunction "1_1") (pintype "unspecified"))
      (node (ref "R45") (pin "1") (pinfunction "1_1") (pintype "unspecified"))
      (node (ref "R47") (pin "1") (pinfunction "1_1") (pintype "unspecified"))
      (node (ref "R51") (pin "1") (pinfunction "1_1") (pintype "unspecified"))
      (node (ref "R52") (pin "1") (pinfunction "1_1") (pintype "unspecified"))
      (node (ref "R54") (pin "1") (pinfunction "1_1") (pintype "unspecified"))
      (node (ref "R56") (pin "1") (pinfunction "1_1") (pintype "unspecified"))
      (node (ref "R61") (pin "1") (pinfunction "1_1") (pintype "unspecified"))
      (node (ref "R62") (pin "1") (pinfunction "1_1") (pintype "unspecified"))
      (node (ref "R63") (pin "1") (pinfunction "1_1") (pintype "unspecified"))
      (node (ref "R64") (pin "2") (pinfunction "2_2") (pintype "unspecified"))
      (node (ref "TP5") (pin "1") (pinfunction "1_1") (pintype "unspecified"))
      (node (ref "U12") (pin "2") (pinfunction "VSS_2") (pintype "unspecified"))
      (node (ref "U13") (pin "2") (pinfunction "-INPUT_2") (pintype "unspecified"))
      (node (ref "U13") (pin "4") (pinfunction "GND_4") (pintype "unspecified"))
      (node (ref "U14") (pin "2") (pinfunction "VSS_2") (pintype "unspecified"))
      (node (ref "U15") (pin "5") (pinfunction "-_In_5") (pintype "unspecified"))
      (node (ref "U16") (pin "5") (pinfunction "VS-_5") (pintype "unspecified"))
      (node (ref "U16") (pin "6") (pinfunction "REF_6") (pintype "unspecified"))
      (node (ref "U17") (pin "2") (pinfunction "2_2") (pintype "unspecified"))
      (node (ref "U2") (pin "2") (pinfunction "GND_2") (pintype "unspecified"))
      (node (ref "U3") (pin "14") (pinfunction "AC/DC#_14") (pintype "unspecified"))
      (node (ref "U3") (pin "16") (pinfunction "GND_16") (pintype "unspecified"))
      (node (ref "U3") (pin "21") (pinfunction "EP_21") (pintype "unspecified"))
      (node (ref "U4") (pin "15") (pinfunction "GND2_15") (pintype "unspecified"))
      (node (ref "U4") (pin "9") (pinfunction "GND2_9") (pintype "unspecified"))
      (node (ref "U5") (pin "13") (pinfunction "GND_13") (pintype "unspecified"))
      (node (ref "U5") (pin "18") (pinfunction "GND_18") (pintype "unspecified"))
      (node (ref "U5") (pin "23") (pinfunction "GND_23") (pintype "unspecified"))
      (node (ref "U5") (pin "28") (pinfunction "GND_28") (pintype "unspecified"))
      (node (ref "U5") (pin "3") (pinfunction "GND_3") (pintype "unspecified"))
      (node (ref "U5") (pin "33") (pinfunction "GND_33") (pintype "unspecified"))
      (node (ref "U5") (pin "38") (pinfunction "GND_38") (pintype "unspecified"))
      (node (ref "U5") (pin "8") (pinfunction "GND_8") (pintype "unspecified"))
      (node (ref "U6") (pin "4") (pinfunction "PGND_4") (pintype "unspecified"))
      (node (ref "U7") (pin "15") (pinfunction "PGND_15") (pintype "unspecified"))
      (node (ref "U7") (pin "2") (pinfunction "GND_2") (pintype "unspecified"))
      (node (ref "U9") (pin "6") (pinfunction "nE_6") (pintype "unspecified"))
      (node (ref "U9") (pin "8") (pinfunction "GND_8") (pintype "unspecified"))
    )
    (net (code "13") (name "I2C0_SCL") (class "Default")
      (node (ref "P5") (pin "3") (pinfunction "3_3") (pintype "unspecified"))
      (node (ref "P6") (pin "3") (pinfunction "3_3") (pintype "unspecified"))
      (node (ref "P7") (pin "3") (pinfunction "3_3") (pintype "unspecified"))
      (node (ref "P9") (pin "2") (pinfunction "2_2") (pintype "input"))
      (node (ref "U5") (pin "27") (pinfunction "GPIO_21_27") (pintype "unspecified"))
    )
    (net (code "14") (name "I2C0_SDA") (class "Default")
      (node (ref "P5") (pin "2") (pinfunction "2_2") (pintype "unspecified"))
      (node (ref "P6") (pin "2") (pinfunction "2_2") (pintype "unspecified"))
      (node (ref "P7") (pin "2") (pinfunction "2_2") (pintype "unspecified"))
      (node (ref "P9") (pin "1") (pinfunction "1_1") (pintype "input"))
      (node (ref "U5") (pin "26") (pinfunction "GPIO_20_26") (pintype "unspecified"))
    )
    (net (code "15") (name "I2C1_SCL") (class "Default")
      (node (ref "P10") (pin "2") (pinfunction "2_2") (pintype "input"))
      (node (ref "P12") (pin "3") (pinfunction "3_3") (pintype "unspecified"))
      (node (ref "P13") (pin "3") (pinfunction "3_3") (pintype "unspecified"))
      (node (ref "P14") (pin "3") (pinfunction "3_3") (pintype "unspecified"))
      (node (ref "U5") (pin "25") (pinfunction "GPIO_19_25") (pintype "unspecified"))
    )
    (net (code "16") (name "I2C1_SDA") (class "Default")
      (node (ref "P10") (pin "1") (pinfunction "1_1") (pintype "input"))
      (node (ref "P12") (pin "2") (pinfunction "2_2") (pintype "unspecified"))
      (node (ref "P13") (pin "2") (pinfunction "2_2") (pintype "unspecified"))
      (node (ref "P14") (pin "2") (pinfunction "2_2") (pintype "unspecified"))
      (node (ref "U5") (pin "24") (pinfunction "GPIO_18_24") (pintype "unspecified"))
    )
    (net (code "17") (name "MCP_CHRG") (class "Default")
      (node (ref "R37") (pin "2") (pinfunction "2_2") (pintype "unspecified"))
      (node (ref "U12") (pin "1") (pinfunction "STAT_1") (pintype "unspecified"))
      (node (ref "U5") (pin "7") (pinfunction "GPIO_5_7") (pintype "unspecified"))
    )
    (net (code "18") (name "MUX_A") (class "Default")
      (node (ref "R41") (pin "2") (pinfunction "2_2") (pintype "unspecified"))
      (node (ref "U5") (pin "14") (pinfunction "GPIO_10_14") (pintype "unspecified"))
      (node (ref "U9") (pin "11") (pinfunction "S1_11") (pintype "unspecified"))
    )
    (net (code "19") (name "MUX_B") (class "Default")
      (node (ref "R40") (pin "2") (pinfunction "2_2") (pintype "unspecified"))
      (node (ref "U5") (pin "15") (pinfunction "GPIO_11_15") (pintype "unspecified"))
      (node (ref "U9") (pin "10") (pinfunction "S2_10") (pintype "unspecified"))
    )
    (net (code "20") (name "MUX_C") (class "Default")
      (node (ref "R39") (pin "2") (pinfunction "2_2") (pintype "unspecified"))
      (node (ref "U5") (pin "16") (pinfunction "GPIO_12_16") (pintype "unspecified"))
      (node (ref "U9") (pin "9") (pinfunction "S3_9") (pintype "unspecified"))
    )
    (net (code "21") (name "Net-(C7-Pad1)") (class "Default")
      (node (ref "C7") (pin "1") (pinfunction "1_1") (pintype "unspecified"))
      (node (ref "R11") (pin "1") (pinfunction "1_1") (pintype "unspecified"))
      (node (ref "R12") (pin "2") (pinfunction "2_2") (pintype "unspecified"))
    )
    (net (code "22") (name "Net-(C23-Pad2)") (class "Default")
      (node (ref "C23") (pin "2") (pinfunction "2_2") (pintype "unspecified"))
      (node (ref "R24") (pin "1") (pinfunction "1_1") (pintype "unspecified"))
      (node (ref "R25") (pin "2") (pinfunction "2_2") (pintype "unspecified"))
    )
    (net (code "23") (name "Net-(C25-Pad2)") (class "Default")
      (node (ref "C25") (pin "2") (pinfunction "2_2") (pintype "unspecified"))
      (node (ref "R38") (pin "1") (pinfunction "1_1") (pintype "unspecified"))
    )
    (net (code "24") (name "Net-(C31-Pad1)") (class "Default")
      (node (ref "C31") (pin "1") (pinfunction "1_1") (pintype "unspecified"))
      (node (ref "U13") (pin "8") (pinfunction "GAIN_8") (pintype "unspecified"))
    )
    (net (code "25") (name "Net-(C31-Pad2)") (class "Default")
      (node (ref "C31") (pin "2") (pinfunction "2_2") (pintype "unspecified"))
      (node (ref "R43") (pin "2") (pinfunction "2_2") (pintype "unspecified"))
    )
    (net (code "26") (name "Net-(C33-Pad1)") (class "Default")
      (node (ref "C33") (pin "1") (pinfunction "1_1") (pintype "unspecified"))
      (node (ref "R44") (pin "1") (pinfunction "1_1") (pintype "unspecified"))
    )
    (net (code "27") (name "Net-(CN1-Pad1)") (class "Default")
      (node (ref "CN1") (pin "1") (pinfunction "1_1") (pintype "unspecified"))
      (node (ref "R5") (pin "1") (pinfunction "1_1") (pintype "unspecified"))
      (node (ref "TP9") (pin "1") (pinfunction "1_1") (pintype "unspecified"))
    )
    (net (code "28") (name "Net-(CN1-Pad2)") (class "Default")
      (node (ref "CN1") (pin "2") (pinfunction "2_2") (pintype "unspecified"))
      (node (ref "R2") (pin "1") (pinfunction "1_1") (pintype "unspecified"))
      (node (ref "R4") (pin "1") (pinfunction "1_1") (pintype "unspecified"))
      (node (ref "TP8") (pin "1") (pinfunction "1_1") (pintype "unspecified"))
    )
    (net (code "29") (name "Net-(CN1-Pad3)") (class "Default")
      (node (ref "CN1") (pin "3") (pinfunction "3_3") (pintype "unspecified"))
      (node (ref "R1") (pin "1") (pinfunction "1_1") (pintype "unspecified"))
      (node (ref "R3") (pin "1") (pinfunction "1_1") (pintype "unspecified"))
      (node (ref "TP7") (pin "1") (pinfunction "1_1") (pintype "unspecified"))
    )
    (net (code "30") (name "Net-(CN2-Pad1)") (class "Default")
      (node (ref "CN2") (pin "1") (pinfunction "1_1") (pintype "unspecified"))
      (node (ref "R16") (pin "2") (pinfunction "2_2") (pintype "unspecified"))
    )
    (net (code "31") (name "Net-(CN2-Pad2)") (class "Default")
      (node (ref "CN2") (pin "2") (pinfunction "2_2") (pintype "unspecified"))
      (node (ref "R17") (pin "2") (pinfunction "2_2") (pintype "unspecified"))
    )
    (net (code "32") (name "Net-(CN3-Pad2)") (class "Default")
      (node (ref "CN3") (pin "2") (pinfunction "2_2") (pintype "unspecified"))
      (node (ref "P1") (pin "2") (pinfunction "2_2") (pintype "input"))
    )
    (net (code "33") (name "Net-(CN3-Pad3)") (class "Default")
      (node (ref "CN3") (pin "3") (pinfunction "3_3") (pintype "unspecified"))
      (node (ref "P1") (pin "1") (pinfunction "1_1") (pintype "input"))
    )
    (net (code "34") (name "Net-(CN5-Pad1)") (class "Default")
      (node (ref "CN5") (pin "1") (pinfunction "1_1") (pintype "unspecified"))
      (node (ref "P2") (pin "2") (pinfunction "2_2") (pintype "input"))
    )
    (net (code "35") (name "Net-(CN7-Pad1)") (class "Default")
      (node (ref "CN7") (pin "1") (pinfunction "1_1") (pintype "unspecified"))
      (node (ref "CN8") (pin "1") (pinfunction "1_1") (pintype "unspecified"))
      (node (ref "U17") (pin "5") (pinfunction "5_5") (pintype "unspecified"))
    )
    (net (code "36") (name "Net-(CN7-Pad2)") (class "Default")
      (node (ref "CN7") (pin "2") (pinfunction "2_2") (pintype "unspecified"))
      (node (ref "CN8") (pin "2") (pinfunction "2_2") (pintype "unspecified"))
      (node (ref "U17") (pin "4") (pinfunction "4_4") (pintype "unspecified"))
    )
    (net (code "37") (name "Net-(D1-Pad1)") (class "Default")
      (node (ref "D1") (pin "1") (pinfunction "1_1") (pintype "unspecified"))
      (node (ref "U7") (pin "6") (pinfunction "L2_6") (pintype "unspecified"))
      (node (ref "U7") (pin "7") (pinfunction "L2_7") (pintype "unspecified"))
    )
    (net (code "38") (name "Net-(D1-Pad2)") (class "Default")
      (node (ref "D1") (pin "2") (pinfunction "2_2") (pintype "unspecified"))
      (node (ref "U7") (pin "8") (pinfunction "L1_8") (pintype "unspecified"))
      (node (ref "U7") (pin "9") (pinfunction "L1_9") (pintype "unspecified"))
    )
    (net (code "39") (name "Net-(D2-+)") (class "Default")
      (node (ref "D2") (pin "2") (pinfunction "+_2") (pintype "unspecified"))
      (node (ref "R28") (pin "2") (pinfunction "2_2") (pintype "unspecified"))
    )
    (net (code "40") (name "Net-(D2--)") (class "Default")
      (node (ref "D2") (pin "1") (pinfunction "-_1") (pintype "unspecified"))
      (node (ref "D5") (pin "1") (pinfunction "-_1") (pintype "unspecified"))
      (node (ref "R29") (pin "1") (pinfunction "1_1") (pintype "unspecified"))
      (node (ref "U7") (pin "12") (pinfunction "EN_12") (pintype "unspecified"))
    )
    (net (code "41") (name "Net-(D4-Pad3)") (class "Default")
      (node (ref "D4") (pin "3") (pinfunction "3_3") (pintype "unspecified"))
      (node (ref "R22") (pin "2") (pinfunction "2_2") (pintype "unspecified"))
    )
    (net (code "42") (name "Net-(D5-+)") (class "Default")
      (node (ref "CN11") (pin "2") (pinfunction "2_2") (pintype "unspecified"))
      (node (ref "D5") (pin "2") (pinfunction "+_2") (pintype "unspecified"))
      (node (ref "R31") (pin "2") (pinfunction "2_2") (pintype "unspecified"))
      (node (ref "R65") (pin "1") (pinfunction "1_1") (pintype "unspecified"))
    )
    (net (code "43") (name "Net-(D7-+)") (class "Default")
      (node (ref "D7") (pin "2") (pinfunction "+_2") (pintype "unspecified"))
      (node (ref "L1") (pin "1") (pinfunction "1_1") (pintype "unspecified"))
      (node (ref "U6") (pin "5") (pinfunction "SW_5") (pintype "unspecified"))
    )
    (net (code "44") (name "Net-(P2-Pad1)") (class "Default")
      (node (ref "P2") (pin "1") (pinfunction "1_1") (pintype "input"))
      (node (ref "R45") (pin "2") (pinfunction "2_2") (pintype "unspecified"))
    )
    (net (code "45") (name "Net-(P9-Pad3)") (class "Default")
      (node (ref "P9") (pin "3") (pinfunction "3_3") (pintype "input"))
      (node (ref "R58") (pin "2") (pinfunction "2_2") (pintype "unspecified"))
    )
    (net (code "46") (name "Net-(P9-Pad4)") (class "Default")
      (node (ref "P9") (pin "4") (pinfunction "4_4") (pintype "input"))
      (node (ref "R57") (pin "2") (pinfunction "2_2") (pintype "unspecified"))
    )
    (net (code "47") (name "Net-(P10-Pad3)") (class "Default")
      (node (ref "P10") (pin "3") (pinfunction "3_3") (pintype "input"))
      (node (ref "R59") (pin "2") (pinfunction "2_2") (pintype "unspecified"))
    )
    (net (code "48") (name "Net-(P10-Pad4)") (class "Default")
      (node (ref "P10") (pin "4") (pinfunction "4_4") (pintype "input"))
      (node (ref "R60") (pin "2") (pinfunction "2_2") (pintype "unspecified"))
    )
    (net (code "49") (name "Net-(Q1-D)") (class "Default")
      (node (ref "BUZZER1") (pin "2") (pinfunction "2_2") (pintype "unspecified"))
      (node (ref "CN14") (pin "1") (pinfunction "1_1") (pintype "unspecified"))
      (node (ref "Q1") (pin "3") (pinfunction "D_3") (pintype "bidirectional"))
    )
    (net (code "50") (name "Net-(Q1-G)") (class "Default")
      (node (ref "Q1") (pin "1") (pinfunction "G_1") (pintype "bidirectional"))
      (node (ref "R15") (pin "1") (pinfunction "1_1") (pintype "unspecified"))
      (node (ref "R56") (pin "2") (pinfunction "2_2") (pintype "unspecified"))
    )
    (net (code "51") (name "Net-(Q2-D)") (class "Default")
      (node (ref "CN9") (pin "2") (pinfunction "2_2") (pintype "unspecified"))
      (node (ref "Q2") (pin "3") (pinfunction "D_3") (pintype "unspecified"))
    )
    (net (code "52") (name "Net-(Q2-G)") (class "Default")
      (node (ref "Q2") (pin "1") (pinfunction "G_1") (pintype "unspecified"))
      (node (ref "R50") (pin "1") (pinfunction "1_1") (pintype "unspecified"))
      (node (ref "R51") (pin "2") (pinfunction "2_2") (pintype "unspecified"))
    )
    (net (code "53") (name "Net-(Q3-D)") (class "Default")
      (node (ref "CN10") (pin "2") (pinfunction "2_2") (pintype "unspecified"))
      (node (ref "Q3") (pin "3") (pinfunction "D_3") (pintype "unspecified"))
    )
    (net (code "54") (name "Net-(Q3-G)") (class "Default")
      (node (ref "Q3") (pin "1") (pinfunction "G_1") (pintype "unspecified"))
      (node (ref "R54") (pin "2") (pinfunction "2_2") (pintype "unspecified"))
      (node (ref "R55") (pin "1") (pinfunction "1_1") (pintype "unspecified"))
    )
    (net (code "55") (name "Net-(Q5-D)") (class "Default")
      (node (ref "Q5") (pin "3") (pinfunction "D_3") (pintype "bidirectional"))
      (node (ref "Q6") (pin "2") (pinfunction "S_2") (pintype "bidirectional"))
    )
    (net (code "56") (name "Net-(Q5-G)") (class "Default")
      (node (ref "Q5") (pin "1") (pinfunction "G_1") (pintype "bidirectional"))
      (node (ref "U11") (pin "4") (pinfunction "DO_4") (pintype "unspecified"))
    )
    (net (code "57") (name "Net-(Q6-G)") (class "Default")
      (node (ref "Q6") (pin "1") (pinfunction "G_1") (pintype "bidirectional"))
      (node (ref "U11") (pin "5") (pinfunction "CO_5") (pintype "unspecified"))
    )
    (net (code "58") (name "Net-(R6-Pad2)") (class "Default")
      (node (ref "R6") (pin "2") (pinfunction "2_2") (pintype "unspecified"))
      (node (ref "R7") (pin "1") (pinfunction "1_1") (pintype "unspecified"))
      (node (ref "R8") (pin "2") (pinfunction "2_2") (pintype "unspecified"))
    )
    (net (code "59") (name "Net-(R43-Pad1)") (class "Default")
      (node (ref "R43") (pin "1") (pinfunction "1_1") (pintype "unspecified"))
      (node (ref "U13") (pin "1") (pinfunction "GAIN_1") (pintype "unspecified"))
    )
    (net (code "60") (name "Net-(R48-Pad1)") (class "Default")
      (node (ref "R48") (pin "1") (pinfunction "1_1") (pintype "unspecified"))
      (node (ref "U16") (pin "3") (pinfunction "RG_3") (pintype "unspecified"))
    )
    (net (code "61") (name "Net-(R48-Pad2)") (class "Default")
      (node (ref "R48") (pin "2") (pinfunction "2_2") (pintype "unspecified"))
      (node (ref "U16") (pin "2") (pinfunction "RG_2") (pintype "unspecified"))
    )
    (net (code "62") (name "Net-(R49-Pad1)") (class "Default")
      (node (ref "R49") (pin "1") (pinfunction "1_1") (pintype "unspecified"))
      (node (ref "U17") (pin "1") (pinfunction "1_1") (pintype "unspecified"))
    )
    (net (code "63") (name "Net-(U3-+IN)") (class "Default")
      (node (ref "R1") (pin "2") (pinfunction "2_2") (pintype "unspecified"))
      (node (ref "U3") (pin "2") (pinfunction "+IN_2") (pintype "unspecified"))
    )
    (net (code "64") (name "Net-(U3--IN)") (class "Default")
      (node (ref "R2") (pin "2") (pinfunction "2_2") (pintype "unspecified"))
      (node (ref "U3") (pin "3") (pinfunction "-IN_3") (pintype "unspecified"))
    )
    (net (code "65") (name "Net-(U3-HPDRIVE)") (class "Default")
      (node (ref "C3") (pin "1") (pinfunction "1_1") (pintype "unspecified"))
      (node (ref "U3") (pin "1") (pinfunction "HPDRIVE_1") (pintype "unspecified"))
    )
    (net (code "66") (name "Net-(U3-HPSENSE)") (class "Default")
      (node (ref "C3") (pin "2") (pinfunction "2_2") (pintype "unspecified"))
      (node (ref "R8") (pin "1") (pinfunction "1_1") (pintype "unspecified"))
      (node (ref "U3") (pin "20") (pinfunction "HPSENSE_20") (pintype "unspecified"))
    )
    (net (code "67") (name "Net-(U3-IAOUT)") (class "Default")
      (node (ref "R11") (pin "2") (pinfunction "2_2") (pintype "unspecified"))
      (node (ref "R7") (pin "2") (pinfunction "2_2") (pintype "unspecified"))
      (node (ref "U3") (pin "19") (pinfunction "IAOUT_19") (pintype "unspecified"))
    )
    (net (code "68") (name "Net-(U3-OPAMP+)") (class "Default")
      (node (ref "C6") (pin "1") (pinfunction "1_1") (pintype "unspecified"))
      (node (ref "R12") (pin "1") (pinfunction "1_1") (pintype "unspecified"))
      (node (ref "U3") (pin "7") (pinfunction "OPAMP+_7") (pintype "unspecified"))
    )
    (net (code "69") (name "Net-(U3-OPAMP-)") (class "Default")
      (node (ref "R10") (pin "1") (pinfunction "1_1") (pintype "unspecified"))
      (node (ref "R9") (pin "2") (pinfunction "2_2") (pintype "unspecified"))
      (node (ref "U3") (pin "9") (pinfunction "OPAMP-_9") (pintype "unspecified"))
    )
    (net (code "70") (name "Net-(U3-REFIN)") (class "Default")
      (node (ref "C8") (pin "2") (pinfunction "2_2") (pintype "unspecified"))
      (node (ref "R13") (pin "2") (pinfunction "2_2") (pintype "unspecified"))
      (node (ref "R14") (pin "1") (pinfunction "1_1") (pintype "unspecified"))
      (node (ref "U3") (pin "18") (pinfunction "REFIN_18") (pintype "unspecified"))
    )
    (net (code "71") (name "Net-(U3-REFOUT)") (class "Default")
      (node (ref "C5") (pin "2") (pinfunction "2_2") (pintype "unspecified"))
      (node (ref "C6") (pin "2") (pinfunction "2_2") (pintype "unspecified"))
      (node (ref "R9") (pin "1") (pinfunction "1_1") (pintype "unspecified"))
      (node (ref "U3") (pin "8") (pinfunction "REFOUT_8") (pintype "unspecified"))
    )
    (net (code "72") (name "Net-(U3-RLD)") (class "Default")
      (node (ref "C4") (pin "1") (pinfunction "1_1") (pintype "unspecified"))
      (node (ref "R5") (pin "2") (pinfunction "2_2") (pintype "unspecified"))
      (node (ref "U3") (pin "5") (pinfunction "RLD_5") (pintype "unspecified"))
    )
    (net (code "73") (name "Net-(U3-RLDFB)") (class "Default")
      (node (ref "C4") (pin "2") (pinfunction "2_2") (pintype "unspecified"))
      (node (ref "U3") (pin "4") (pinfunction "RLDFB_4") (pintype "unspecified"))
    )
    (net (code "74") (name "Net-(U3-SW)") (class "Default")
      (node (ref "C5") (pin "1") (pinfunction "1_1") (pintype "unspecified"))
      (node (ref "R6") (pin "1") (pinfunction "1_1") (pintype "unspecified"))
      (node (ref "U3") (pin "6") (pinfunction "SW_6") (pintype "unspecified"))
    )
    (net (code "75") (name "Net-(U4-DD+)") (class "Default")
      (node (ref "R17") (pin "1") (pinfunction "1_1") (pintype "unspecified"))
      (node (ref "U4") (pin "10") (pinfunction "DD+_10") (pintype "unspecified"))
    )
    (net (code "76") (name "Net-(U4-DD-)") (class "Default")
      (node (ref "R16") (pin "1") (pinfunction "1_1") (pintype "unspecified"))
      (node (ref "U4") (pin "11") (pinfunction "DD-_11") (pintype "unspecified"))
    )
    (net (code "77") (name "Net-(U4-PDEN)") (class "Default")
      (node (ref "C10") (pin "1") (pinfunction "1_1") (pintype "unspecified"))
      (node (ref "U4") (pin "3") (pinfunction "VDD1_3") (pintype "unspecified"))
      (node (ref "U4") (pin "4") (pinfunction "PDEN_4") (pintype "unspecified"))
      (node (ref "U4") (pin "5") (pinfunction "SPU_5") (pintype "unspecified"))
    )
    (net (code "78") (name "Net-(U4-UD+)") (class "Default")
      (node (ref "R19") (pin "2") (pinfunction "2_2") (pintype "unspecified"))
      (node (ref "U4") (pin "7") (pinfunction "UD+_7") (pintype "unspecified"))
    )
    (net (code "79") (name "Net-(U4-UD–)") (class "Default")
      (node (ref "R18") (pin "2") (pinfunction "2_2") (pintype "unspecified"))
      (node (ref "U4") (pin "6") (pinfunction "UD–_6") (pintype "unspecified"))
    )
    (net (code "80") (name "Net-(U6-COMP)") (class "Default")
      (node (ref "R38") (pin "2") (pinfunction "2_2") (pintype "unspecified"))
      (node (ref "U6") (pin "1") (pinfunction "COMP_1") (pintype "unspecified"))
    )
    (net (code "81") (name "Net-(U6-FB)") (class "Default")
      (node (ref "R26") (pin "2") (pinfunction "2_2") (pintype "unspecified"))
      (node (ref "R27") (pin "1") (pinfunction "1_1") (pintype "unspecified"))
      (node (ref "U6") (pin "2") (pinfunction "FB_2") (pintype "unspecified"))
    )
    (net (code "82") (name "Net-(U6-SS)") (class "Default")
      (node (ref "C30") (pin "2") (pinfunction "2_2") (pintype "unspecified"))
      (node (ref "U6") (pin "8") (pinfunction "SS_8") (pintype "unspecified"))
    )
    (net (code "83") (name "Net-(U7-PG)") (class "Default")
      (node (ref "R30") (pin "2") (pinfunction "2_2") (pintype "unspecified"))
      (node (ref "U7") (pin "14") (pinfunction "PG_14") (pintype "unspecified"))
    )
    (net (code "84") (name "Net-(U7-PS{slash}SYNC)") (class "Default")
      (node (ref "C14") (pin "1") (pinfunction "1_1") (pintype "unspecified"))
      (node (ref "U7") (pin "1") (pinfunction "VINA_1") (pintype "unspecified"))
      (node (ref "U7") (pin "13") (pinfunction "PS/SYNC_13") (pintype "unspecified"))
    )
    (net (code "85") (name "Net-(U9-Y0)") (class "Default")
      (node (ref "S1") (pin "2") (pinfunction "2_2") (pintype "unspecified"))
      (node (ref "U9") (pin "13") (pinfunction "Y0_13") (pintype "unspecified"))
    )
    (net (code "86") (name "Net-(U9-Y1)") (class "Default")
      (node (ref "S1") (pin "4") (pinfunction "4_4") (pintype "unspecified"))
      (node (ref "U9") (pin "14") (pinfunction "Y1_14") (pintype "unspecified"))
    )
    (net (code "87") (name "Net-(U9-Y2)") (class "Default")
      (node (ref "S1") (pin "8") (pinfunction "8_8") (pintype "unspecified"))
      (node (ref "U9") (pin "15") (pinfunction "Y2_15") (pintype "unspecified"))
    )
    (net (code "88") (name "Net-(U9-Y3)") (class "Default")
      (node (ref "S1") (pin "6") (pinfunction "6_6") (pintype "unspecified"))
      (node (ref "U9") (pin "12") (pinfunction "Y3_12") (pintype "unspecified"))
    )
    (net (code "89") (name "Net-(U11-VDD)") (class "Default")
      (node (ref "C24") (pin "2") (pinfunction "2_2") (pintype "unspecified"))
      (node (ref "R34") (pin "1") (pinfunction "1_1") (pintype "unspecified"))
      (node (ref "U11") (pin "2") (pinfunction "VDD_2") (pintype "unspecified"))
    )
    (net (code "90") (name "Net-(U11-VM)") (class "Default")
      (node (ref "R35") (pin "2") (pinfunction "2_2") (pintype "unspecified"))
      (node (ref "U11") (pin "1") (pinfunction "VM_1") (pintype "unspecified"))
    )
    (net (code "91") (name "Net-(U12-PROG)") (class "Default")
      (node (ref "R36") (pin "2") (pinfunction "2_2") (pintype "unspecified"))
      (node (ref "U12") (pin "5") (pinfunction "PROG_5") (pintype "unspecified"))
    )
    (net (code "92") (name "Net-(U13-+INPUT)") (class "Default")
      (node (ref "R42") (pin "2") (pinfunction "2_2") (pintype "unspecified"))
      (node (ref "U13") (pin "3") (pinfunction "+INPUT_3") (pintype "unspecified"))
    )
    (net (code "93") (name "Net-(U13-BYPASS)") (class "Default")
      (node (ref "C32") (pin "2") (pinfunction "2_2") (pintype "unspecified"))
      (node (ref "U13") (pin "7") (pinfunction "BYPASS_7") (pintype "unspecified"))
    )
    (net (code "94") (name "Net-(U13-VOUT)") (class "Default")
      (node (ref "C34") (pin "+") (pinfunction "+_+") (pintype "bidirectional"))
      (node (ref "R44") (pin "2") (pinfunction "2_2") (pintype "unspecified"))
      (node (ref "U13") (pin "5") (pinfunction "VOUT_5") (pintype "unspecified"))
    )
    (net (code "95") (name "Net-(U14-VIN+)") (class "Default")
      (node (ref "C34") (pin "-") (pinfunction "-_-") (pintype "bidirectional"))
      (node (ref "P2") (pin "3") (pinfunction "3_3") (pintype "input"))
      (node (ref "P2") (pin "4") (pinfunction "4_4") (pintype "input"))
      (node (ref "U14") (pin "3") (pinfunction "VIN+_3") (pintype "unspecified"))
    )
    (net (code "96") (name "Net-(U14-VIN-)") (class "Default")
      (node (ref "R46") (pin "2") (pinfunction "2_2") (pintype "unspecified"))
      (node (ref "U14") (pin "1") (pinfunction "VOUT_1") (pintype "output"))
      (node (ref "U14") (pin "4") (pinfunction "VIN-_4") (pintype "unspecified"))
    )
    (net (code "97") (name "Net-(U15-+_In)") (class "Default")
      (node (ref "C37") (pin "2") (pinfunction "2_2") (pintype "unspecified"))
      (node (ref "P15") (pin "3") (pinfunction "3_3") (pintype "input"))
      (node (ref "P15") (pin "4") (pinfunction "4_4") (pintype "input"))
      (node (ref "U15") (pin "2") (pinfunction "+_In_2") (pintype "unspecified"))
    )
    (net (code "98") (name "Net-(U15-+_Out)") (class "Default")
      (node (ref "TP15") (pin "1") (pinfunction "1_1") (pintype "unspecified"))
      (node (ref "U15") (pin "3") (pinfunction "+_Out_3") (pintype "unspecified"))
      (node (ref "U16") (pin "4") (pinfunction "IN+_4") (pintype "unspecified"))
    )
    (net (code "99") (name "Net-(U16-IN-)") (class "Default")
      (node (ref "TP16") (pin "1") (pinfunction "1_1") (pintype "unspecified"))
      (node (ref "U15") (pin "1") (pinfunction "-_Out_1") (pintype "unspecified"))
      (node (ref "U15") (pin "4") (pinfunction "-_Out_4") (pintype "unspecified"))
      (node (ref "U16") (pin "1") (pinfunction "IN-_1") (pintype "unspecified"))
    )
    (net (code "100") (name "Net-(U16-VS+)") (class "Default")
      (node (ref "C38") (pin "1") (pinfunction "1_1") (pintype "unspecified"))
      (node (ref "P3") (pin "3") (pinfunction "3_3") (pintype "input"))
      (node (ref "P3") (pin "4") (pinfunction "4_4") (pintype "input"))
      (node (ref "U16") (pin "8") (pinfunction "VS+_8") (pintype "unspecified"))
    )
    (net (code "101") (name "Net-(USB1-D+)") (class "Default")
      (node (ref "R19") (pin "1") (pinfunction "1_1") (pintype "unspecified"))
      (node (ref "USB1") (pin "3") (pinfunction "D+_3") (pintype "unspecified"))
    )
    (net (code "102") (name "Net-(USB1-D-)") (class "Default")
      (node (ref "R18") (pin "1") (pinfunction "1_1") (pintype "unspecified"))
      (node (ref "USB1") (pin "2") (pinfunction "D-_2") (pintype "unspecified"))
    )
    (net (code "103") (name "PICO_AUX") (class "Default")
      (node (ref "D8") (pin "3") (pinfunction "3_3") (pintype "unspecified"))
      (node (ref "U5") (pin "34") (pinfunction "GPIO_28_34") (pintype "unspecified"))
      (node (ref "U9") (pin "3") (pinfunction "Z_3") (pintype "unspecified"))
    )
    (net (code "104") (name "PICO_BPM_AN") (class "Default")
      (node (ref "D9") (pin "3") (pinfunction "3_3") (pintype "unspecified"))
      (node (ref "TP14") (pin "1") (pinfunction "1_1") (pintype "unspecified"))
      (node (ref "U16") (pin "7") (pinfunction "VOUT_7") (pintype "output"))
      (node (ref "U5") (pin "31") (pinfunction "GPIO_26_31") (pintype "unspecified"))
    )
    (net (code "105") (name "PICO_BPM_BTN") (class "Default")
      (node (ref "R49") (pin "2") (pinfunction "2_2") (pintype "unspecified"))
      (node (ref "U5") (pin "10") (pinfunction "GPIO_7_10") (pintype "unspecified"))
    )
    (net (code "106") (name "PICO_BPM_PUMP") (class "Default")
      (node (ref "R50") (pin "2") (pinfunction "2_2") (pintype "unspecified"))
      (node (ref "U5") (pin "11") (pinfunction "GPIO_8_11") (pintype "unspecified"))
    )
    (net (code "107") (name "PICO_BPM_PWR") (class "Default")
      (node (ref "U5") (pin "9") (pinfunction "GPIO_6_9") (pintype "unspecified"))
      (node (ref "U6") (pin "3") (pinfunction "EN_3") (pintype "unspecified"))
    )
    (net (code "108") (name "PICO_BPM_VALVE") (class "Default")
      (node (ref "R55") (pin "2") (pinfunction "2_2") (pintype "unspecified"))
      (node (ref "U5") (pin "12") (pinfunction "GPIO_9_12") (pintype "unspecified"))
    )
    (net (code "109") (name "PICO_BUZZ") (class "Default")
      (node (ref "R15") (pin "2") (pinfunction "2_2") (pintype "unspecified"))
      (node (ref "U5") (pin "20") (pinfunction "GPIO_15_20") (pintype "unspecified"))
    )
    (net (code "110") (name "PICO_EBT") (class "Default")
      (node (ref "P4") (pin "1") (pinfunction "1_1") (pintype "unspecified"))
      (node (ref "U5") (pin "29") (pinfunction "GPIO_22_29") (pintype "unspecified"))
    )
    (net (code "111") (name "PICO_ECG_AN") (class "Default")
      (node (ref "C7") (pin "2") (pinfunction "2_2") (pintype "unspecified"))
      (node (ref "CN4") (pin "3") (pinfunction "3_3") (pintype "unspecified"))
      (node (ref "R10") (pin "2") (pinfunction "2_2") (pintype "unspecified"))
      (node (ref "TP6") (pin "1") (pinfunction "1_1") (pintype "unspecified"))
      (node (ref "U3") (pin "10") (pinfunction "OUT_10") (pintype "unspecified"))
      (node (ref "U5") (pin "32") (pinfunction "GPIO_27_32") (pintype "unspecified"))
    )
    (net (code "112") (name "PICO_ECG_LN") (class "Default")
      (node (ref "CN4") (pin "4") (pinfunction "4_4") (pintype "unspecified"))
      (node (ref "R63") (pin "2") (pinfunction "2_2") (pintype "unspecified"))
      (node (ref "U3") (pin "11") (pinfunction "LOD-_11") (pintype "unspecified"))
      (node (ref "U9") (pin "5") (pinfunction "Y5_5") (pintype "unspecified"))
    )
    (net (code "113") (name "PICO_ECG_LP") (class "Default")
      (node (ref "CN4") (pin "5") (pinfunction "5_5") (pintype "unspecified"))
      (node (ref "R62") (pin "2") (pinfunction "2_2") (pintype "unspecified"))
      (node (ref "U3") (pin "12") (pinfunction "LOD+_12") (pintype "unspecified"))
      (node (ref "U9") (pin "1") (pinfunction "Y4_1") (pintype "unspecified"))
    )
    (net (code "114") (name "PICO_ECG_SIG") (class "Default")
      (node (ref "CN4") (pin "6") (pinfunction "6_6") (pintype "unspecified"))
      (node (ref "R61") (pin "2") (pinfunction "2_2") (pintype "unspecified"))
      (node (ref "U3") (pin "13") (pinfunction "SDN#_13") (pintype "unspecified"))
      (node (ref "U5") (pin "17") (pinfunction "GPIO_13_17") (pintype "unspecified"))
    )
    (net (code "115") (name "PICO_ENA") (class "Default")
      (node (ref "P4") (pin "3") (pinfunction "3_3") (pintype "unspecified"))
      (node (ref "U5") (pin "21") (pinfunction "GPIO_16_21") (pintype "unspecified"))
    )
    (net (code "116") (name "PICO_ENB") (class "Default")
      (node (ref "P4") (pin "2") (pinfunction "2_2") (pintype "unspecified"))
      (node (ref "U5") (pin "22") (pinfunction "GPIO_17_22") (pintype "unspecified"))
    )
    (net (code "117") (name "PICO_LED") (class "Default")
      (node (ref "CN13") (pin "2") (pinfunction "2_2") (pintype "unspecified"))
      (node (ref "U5") (pin "19") (pinfunction "GPIO_14_19") (pintype "unspecified"))
    )
    (net (code "118") (name "POWER_LATCH") (class "Default")
      (node (ref "R28") (pin "1") (pinfunction "1_1") (pintype "unspecified"))
      (node (ref "U5") (pin "5") (pinfunction "GPIO_3_5") (pintype "unspecified"))
    )
    (net (code "119") (name "SIG_CHARGE") (class "Default")
      (node (ref "R32") (pin "2") (pinfunction "2_2") (pintype "unspecified"))
      (node (ref "R33") (pin "1") (pinfunction "1_1") (pintype "unspecified"))
      (node (ref "U5") (pin "6") (pinfunction "GPIO_4_6") (pintype "unspecified"))
    )
    (net (code "120") (name "USB_GND") (class "Default")
      (node (ref "C10") (pin "2") (pinfunction "2_2") (pintype "unspecified"))
      (node (ref "C11") (pin "1") (pinfunction "1_1") (pintype "unspecified"))
      (node (ref "PWR1") (pin "2") (pinfunction "-VIN(GND)_2") (pintype "unspecified"))
      (node (ref "U4") (pin "2") (pinfunction "GND1_2") (pintype "unspecified"))
      (node (ref "U4") (pin "8") (pinfunction "GND1_8") (pintype "unspecified"))
      (node (ref "USB1") (pin "4") (pinfunction "GND_4") (pintype "unspecified"))
      (node (ref "USB1") (pin "5") (pinfunction "5_5") (pintype "unspecified"))
      (node (ref "USB1") (pin "6") (pinfunction "6_6") (pintype "unspecified"))
    )
    (net (code "121") (name "VBAT") (class "Default")
      (node (ref "C15") (pin "2") (pinfunction "2_2") (pintype "unspecified"))
      (node (ref "C16") (pin "2") (pinfunction "2_2") (pintype "unspecified"))
      (node (ref "C27") (pin "1") (pinfunction "1_1") (pintype "unspecified"))
      (node (ref "C29") (pin "1") (pinfunction "1_1") (pintype "unspecified"))
      (node (ref "CN11") (pin "1") (pinfunction "1_1") (pintype "unspecified"))
      (node (ref "CN12") (pin "1") (pinfunction "1_1") (pintype "unspecified"))
      (node (ref "L1") (pin "2") (pinfunction "2_2") (pintype "unspecified"))
      (node (ref "R34") (pin "2") (pinfunction "2_2") (pintype "unspecified"))
      (node (ref "R53") (pin "2") (pinfunction "2_2") (pintype "unspecified"))
      (node (ref "TP2") (pin "1") (pinfunction "1_1") (pintype "unspecified"))
      (node (ref "U12") (pin "3") (pinfunction "VBAT_3") (pintype "unspecified"))
      (node (ref "U6") (pin "6") (pinfunction "IN_6") (pintype "unspecified"))
      (node (ref "U6") (pin "7") (pinfunction "FREQ_7") (pintype "unspecified"))
      (node (ref "U7") (pin "10") (pinfunction "VIN_10") (pintype "unspecified"))
      (node (ref "U7") (pin "11") (pinfunction "VIN_11") (pintype "unspecified"))
    )
    (net (code "122") (name "VBAT_NEG") (class "Default")
      (node (ref "C24") (pin "1") (pinfunction "1_1") (pintype "unspecified"))
      (node (ref "CN12") (pin "2") (pinfunction "2_2") (pintype "unspecified"))
      (node (ref "Q5") (pin "2") (pinfunction "S_2") (pintype "bidirectional"))
      (node (ref "TP3") (pin "1") (pinfunction "1_1") (pintype "unspecified"))
      (node (ref "U11") (pin "3") (pinfunction "VSS_3") (pintype "unspecified"))
    )
    (net (code "123") (name "unconnected-(D4-Pad2)") (class "Default")
      (node (ref "D4") (pin "2") (pinfunction "2_2") (pintype "unspecified+no_connect"))
    )
    (net (code "124") (name "unconnected-(R43-Pad3)") (class "Default")
      (node (ref "R43") (pin "3") (pinfunction "3_3") (pintype "unspecified+no_connect"))
    )
    (net (code "125") (name "unconnected-(R48-Pad3)") (class "Default")
      (node (ref "R48") (pin "3") (pinfunction "3_3") (pintype "unspecified+no_connect"))
    )
    (net (code "126") (name "unconnected-(U2-NC-Pad4)") (class "Default")
      (node (ref "U2") (pin "4") (pinfunction "NC_4") (pintype "unspecified+no_connect"))
    )
    (net (code "127") (name "unconnected-(U2-NC-Pad5)") (class "Default")
      (node (ref "U2") (pin "5") (pinfunction "NC_5") (pintype "unspecified+no_connect"))
    )
    (net (code "128") (name "unconnected-(U5-+-Pad44)") (class "Default")
      (node (ref "U5") (pin "44") (pinfunction "+_44") (pintype "unspecified+no_connect"))
    )
    (net (code "129") (name "unconnected-(U5---Pad45)") (class "Default")
      (node (ref "U5") (pin "45") (pinfunction "-_45") (pintype "unspecified+no_connect"))
    )
    (net (code "130") (name "unconnected-(U5-3v3_EN-Pad37)") (class "Default")
      (node (ref "U5") (pin "37") (pinfunction "3v3_EN_37") (pintype "unspecified+no_connect"))
    )
    (net (code "131") (name "unconnected-(U5-ADC_VREF-Pad35)") (class "Default")
      (node (ref "U5") (pin "35") (pinfunction "ADC_VREF_35") (pintype "unspecified+no_connect"))
    )
    (net (code "132") (name "unconnected-(U5-GND-Pad46)") (class "Default")
      (node (ref "U5") (pin "46") (pinfunction "GND_46") (pintype "unspecified+no_connect"))
    )
    (net (code "133") (name "unconnected-(U5-GND-Pad48)") (class "Default")
      (node (ref "U5") (pin "48") (pinfunction "GND_48") (pintype "unspecified+no_connect"))
    )
    (net (code "134") (name "unconnected-(U5-GND-Pad49)") (class "Default")
      (node (ref "U5") (pin "49") (pinfunction "GND_49") (pintype "unspecified+no_connect"))
    )
    (net (code "135") (name "unconnected-(U5-GND-Pad50)") (class "Default")
      (node (ref "U5") (pin "50") (pinfunction "GND_50") (pintype "unspecified+no_connect"))
    )
    (net (code "136") (name "unconnected-(U5-GPIO_0-Pad1)") (class "Default")
      (node (ref "U5") (pin "1") (pinfunction "GPIO_0_1") (pintype "unspecified+no_connect"))
    )
    (net (code "137") (name "unconnected-(U5-GPIO_1-Pad2)") (class "Default")
      (node (ref "U5") (pin "2") (pinfunction "GPIO_1_2") (pintype "unspecified+no_connect"))
    )
    (net (code "138") (name "unconnected-(U5-RUN-Pad30)") (class "Default")
      (node (ref "U5") (pin "30") (pinfunction "RUN_30") (pintype "unspecified+no_connect"))
    )
    (net (code "139") (name "unconnected-(U5-VBUS-Pad40)") (class "Default")
      (node (ref "U5") (pin "40") (pinfunction "VBUS_40") (pintype "unspecified+no_connect"))
    )
    (net (code "140") (name "unconnected-(U5-VCC-Pad47)") (class "Default")
      (node (ref "U5") (pin "47") (pinfunction "VCC_47") (pintype "unspecified+no_connect"))
    )
    (net (code "141") (name "unconnected-(U5-VSYS-Pad39)") (class "Default")
      (node (ref "U5") (pin "39") (pinfunction "VSYS_39") (pintype "unspecified+no_connect"))
    )
    (net (code "142") (name "unconnected-(U9-NC-Pad7)") (class "Default")
      (node (ref "U9") (pin "7") (pinfunction "NC_7") (pintype "unspecified+no_connect"))
    )
    (net (code "143") (name "unconnected-(U9-Y6-Pad2)") (class "Default")
      (node (ref "U9") (pin "2") (pinfunction "Y6_2") (pintype "unspecified+no_connect"))
    )
    (net (code "144") (name "unconnected-(U9-Y7-Pad4)") (class "Default")
      (node (ref "U9") (pin "4") (pinfunction "Y7_4") (pintype "unspecified+no_connect"))
    )
    (net (code "145") (name "unconnected-(U15-N{slash}C-Pad6)") (class "Default")
      (node (ref "U15") (pin "6") (pinfunction "N/C_6") (pintype "unspecified+no_connect"))
    )
    (net (code "146") (name "unconnected-(U17-NC-Pad3)") (class "Default")
      (node (ref "U17") (pin "3") (pinfunction "NC_3") (pintype "unspecified+no_connect"))
    )
    (net (code "147") (name "unconnected-(U17-Pad6)") (class "Default")
      (node (ref "U17") (pin "6") (pinfunction "6_6") (pintype "unspecified+no_connect"))
    )
  )
)
